# galvanika-board-2_2.net
KiCad netlist of a schematic drawn in EAGLE
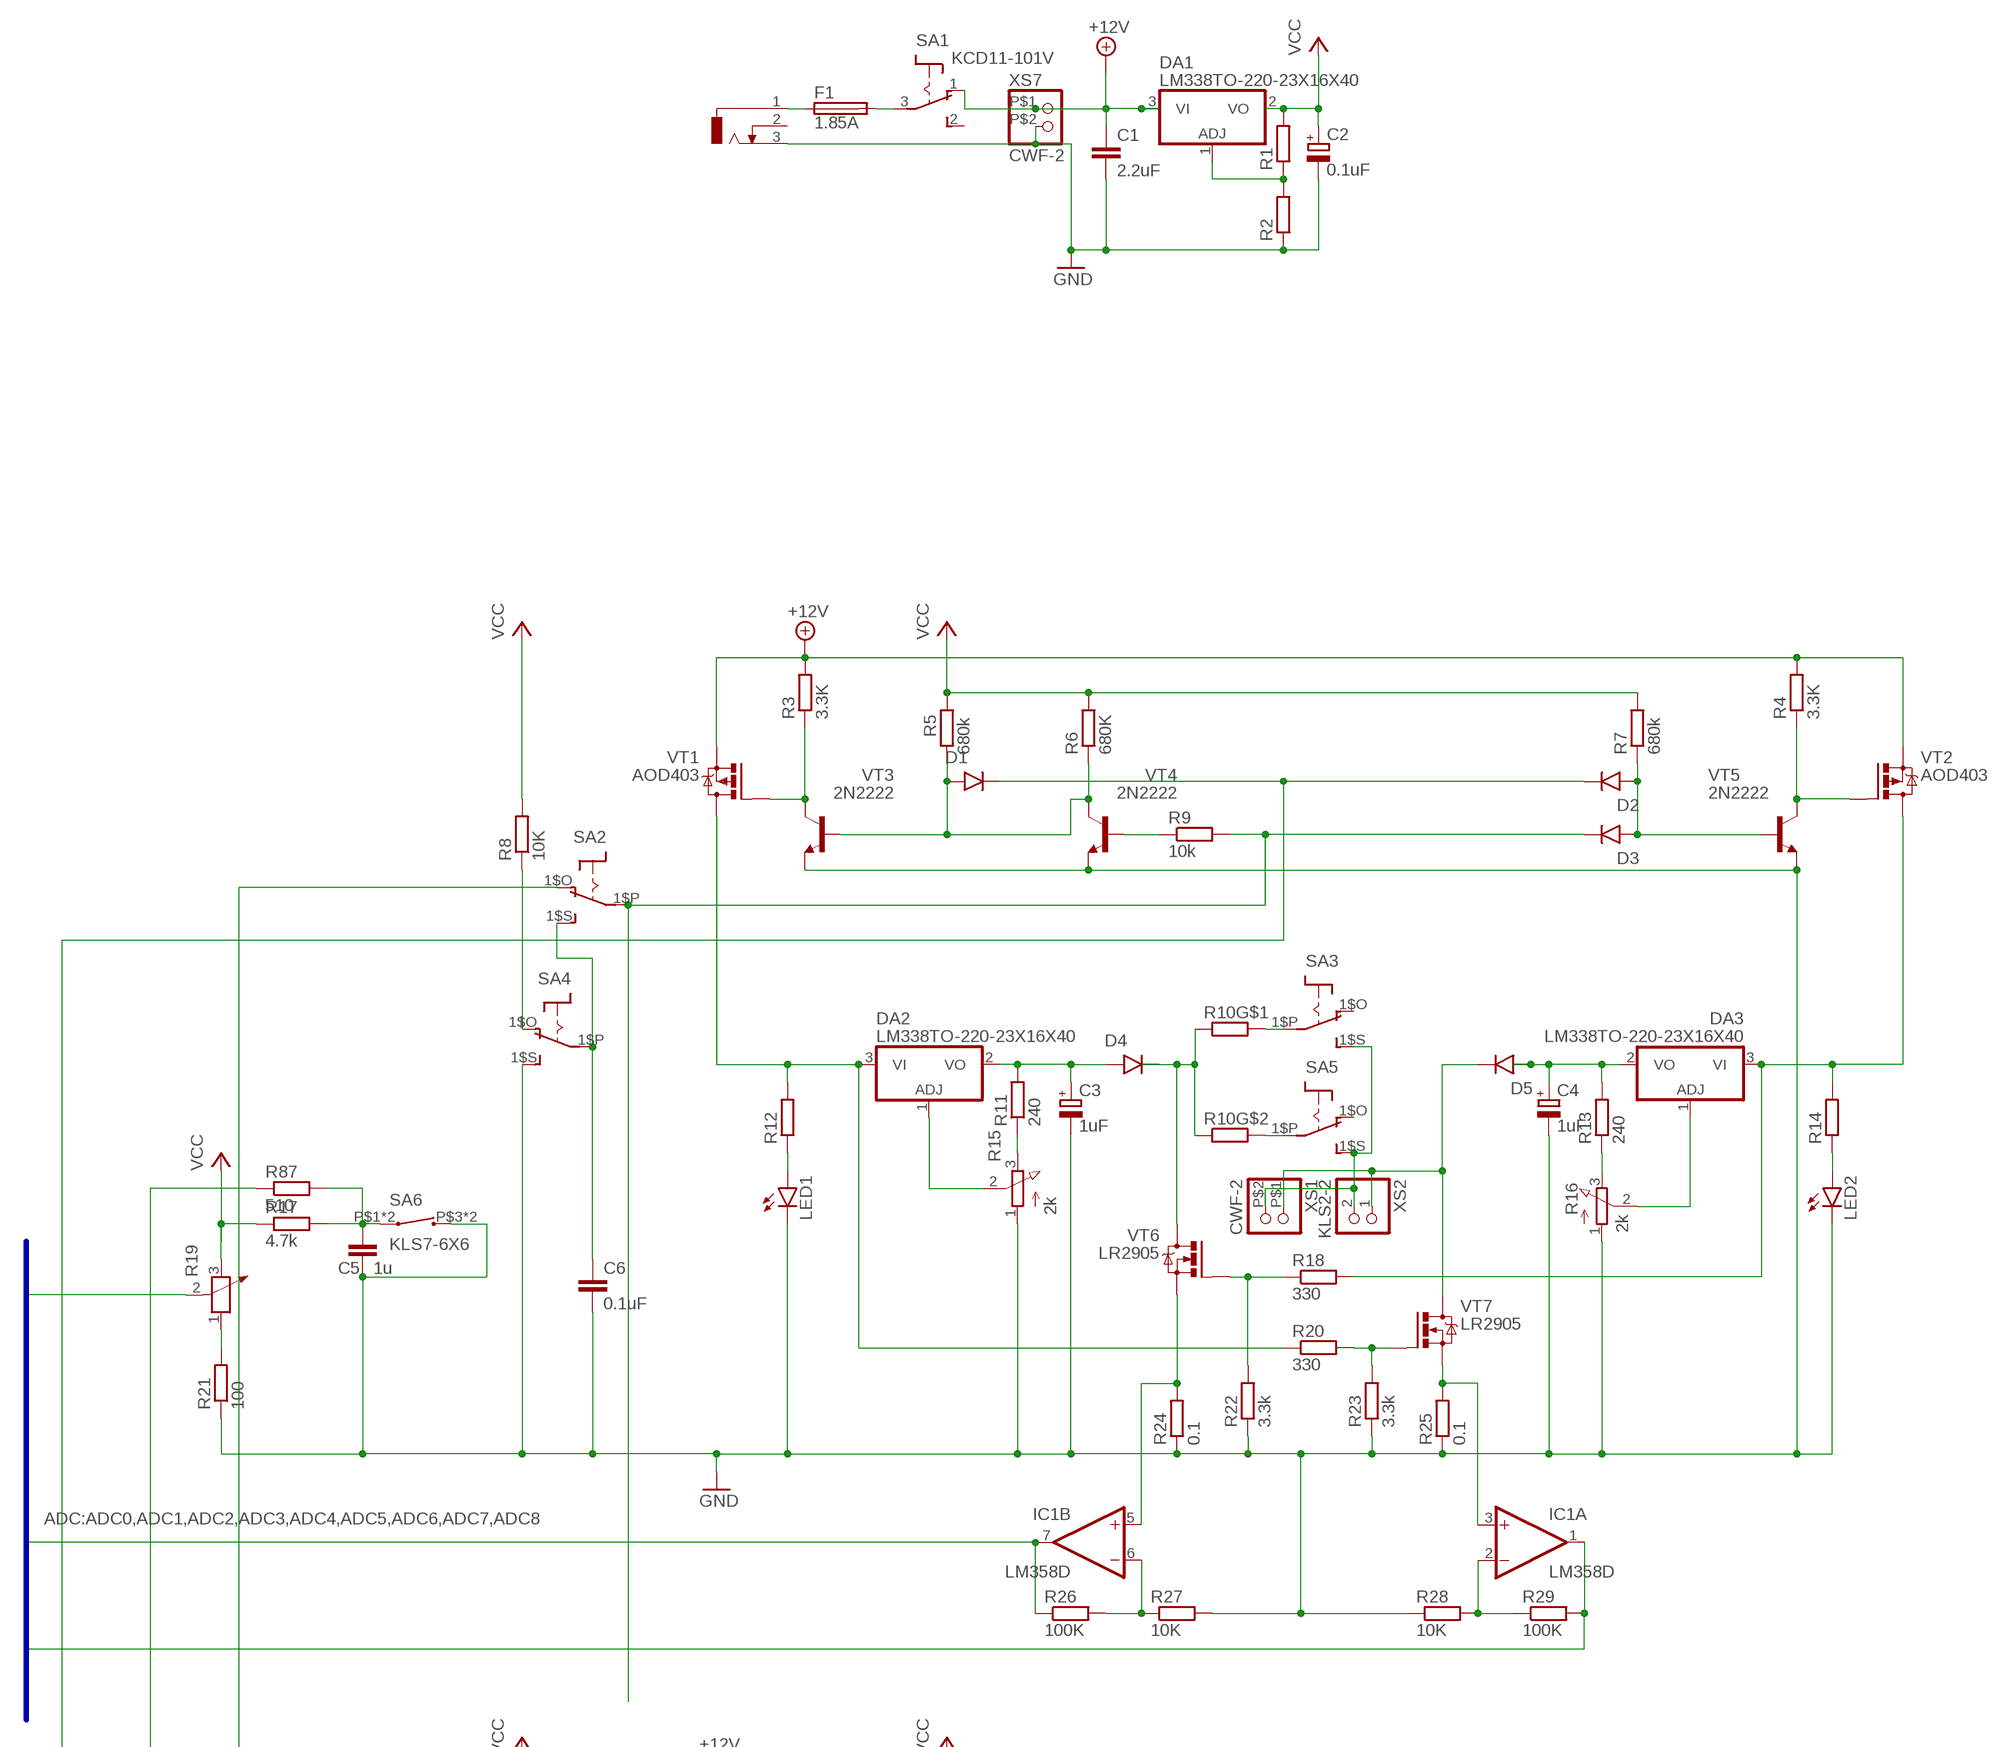
[diagram p0: schematic, sheet 1, part 1 of 2]
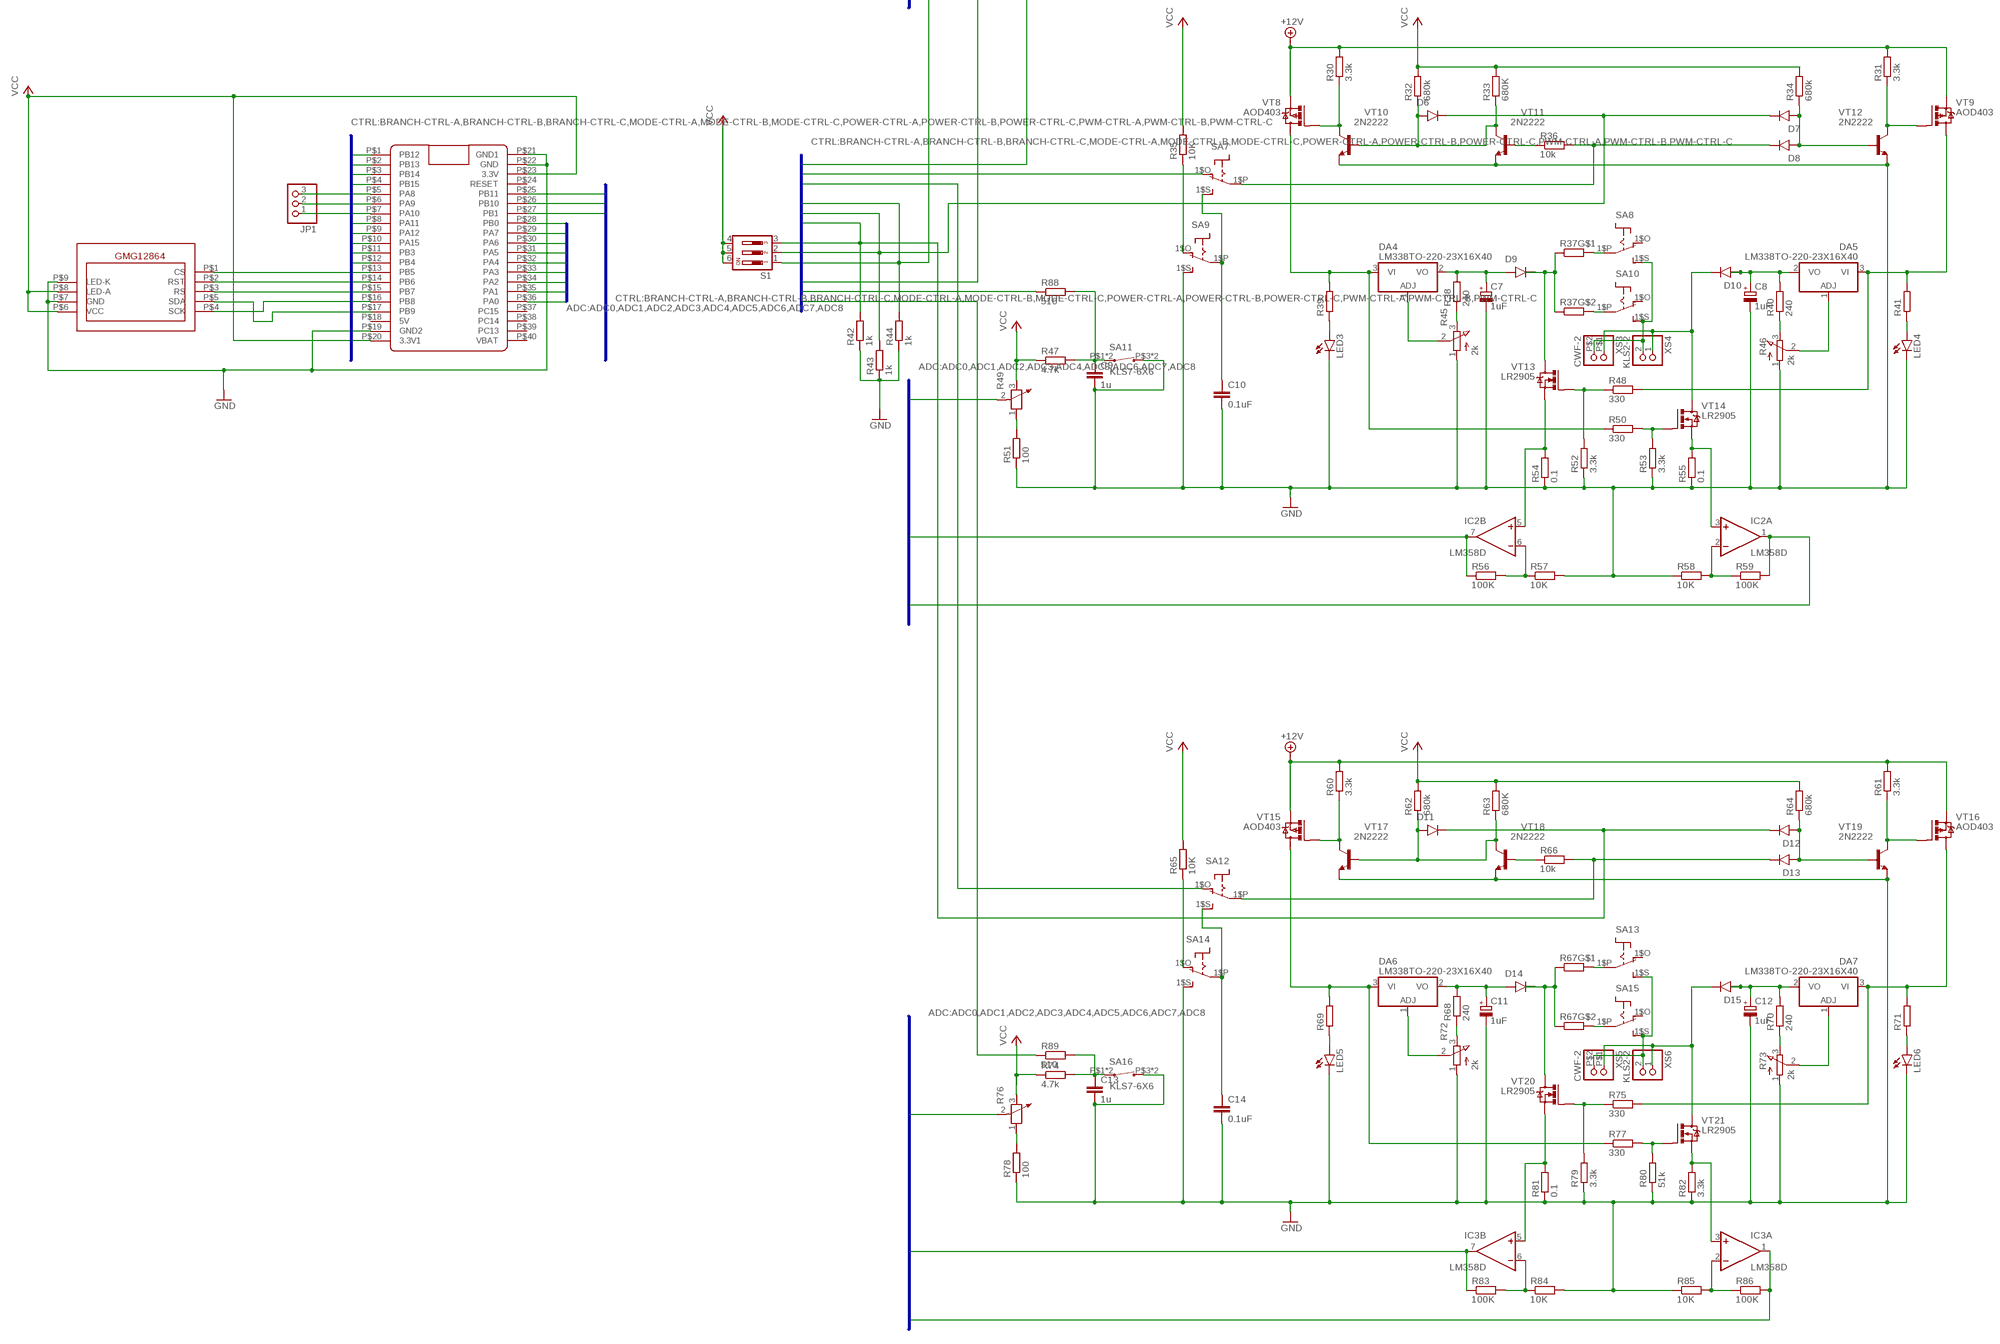
[diagram p1: schematic, sheet 1, part 2 of 2]

(export (version "E")
  (design (tool "Eeschema 10.0.6"))
  (components
    (comp (ref "C1")
      (value "2.2uF")
      (footprint "eagle-import:C025-025X050")
      (libsource (lib "eagle-import") (part "C-EU025-025X050"))
    )
    (comp (ref "C2")
      (value "0.1uF")
      (footprint "eagle-import:E2,5-5")
      (libsource (lib "eagle-import") (part "rcl_334_CPOL-EUE2.5-5"))
    )
    (comp (ref "C3")
      (value "1uF")
      (footprint "eagle-import:E5-4")
      (libsource (lib "eagle-import") (part "CPOL-EUE5-4"))
    )
    (comp (ref "C4")
      (value "1uF")
      (footprint "eagle-import:E5-4")
      (libsource (lib "eagle-import") (part "CPOL-EUE5-4"))
    )
    (comp (ref "C5")
      (value "1u")
      (footprint "eagle-import:C1206")
      (libsource (lib "eagle-import") (part "C-EUC1206"))
    )
    (comp (ref "C6")
      (value "0.1uF")
      (footprint "eagle-import:C1206")
      (libsource (lib "eagle-import") (part "C-EUC1206"))
    )
    (comp (ref "C7")
      (value "1uF")
      (footprint "eagle-import:E5-4")
      (libsource (lib "eagle-import") (part "CPOL-EUE5-4"))
    )
    (comp (ref "C8")
      (value "1uF")
      (footprint "eagle-import:E5-4")
      (libsource (lib "eagle-import") (part "CPOL-EUE5-4"))
    )
    (comp (ref "C9")
      (value "1u")
      (footprint "eagle-import:C1206")
      (libsource (lib "eagle-import") (part "C-EUC1206"))
    )
    (comp (ref "C10")
      (value "0.1uF")
      (footprint "eagle-import:C1206")
      (libsource (lib "eagle-import") (part "C-EUC1206"))
    )
    (comp (ref "C11")
      (value "1uF")
      (footprint "eagle-import:E5-4")
      (libsource (lib "eagle-import") (part "CPOL-EUE5-4"))
    )
    (comp (ref "C12")
      (value "1uF")
      (footprint "eagle-import:E5-4")
      (libsource (lib "eagle-import") (part "CPOL-EUE5-4"))
    )
    (comp (ref "C13")
      (value "1u")
      (footprint "eagle-import:C1206")
      (libsource (lib "eagle-import") (part "C-EUC1206"))
    )
    (comp (ref "C14")
      (value "0.1uF")
      (footprint "eagle-import:C1206")
      (libsource (lib "eagle-import") (part "C-EUC1206"))
    )
    (comp (ref "D1")
      (value "1N4001")
      (footprint "eagle-import:DO41-10")
      (libsource (lib "eagle-import") (part "1N4001"))
    )
    (comp (ref "D2")
      (value "1N4001")
      (footprint "eagle-import:DO41-10")
      (libsource (lib "eagle-import") (part "1N4001"))
    )
    (comp (ref "D3")
      (value "1N4001")
      (footprint "eagle-import:DO41-10")
      (libsource (lib "eagle-import") (part "1N4001"))
    )
    (comp (ref "D4")
      (value "1N4001")
      (footprint "eagle-import:DO41-10")
      (libsource (lib "eagle-import") (part "1N4001"))
    )
    (comp (ref "D5")
      (value "1N4001")
      (footprint "eagle-import:DO41-10")
      (libsource (lib "eagle-import") (part "1N4001"))
    )
    (comp (ref "D6")
      (value "1N4001")
      (footprint "eagle-import:DO41-10")
      (libsource (lib "eagle-import") (part "1N4001"))
    )
    (comp (ref "D7")
      (value "1N4001")
      (footprint "eagle-import:DO41-10")
      (libsource (lib "eagle-import") (part "1N4001"))
    )
    (comp (ref "D8")
      (value "1N4001")
      (footprint "eagle-import:DO41-10")
      (libsource (lib "eagle-import") (part "1N4001"))
    )
    (comp (ref "D9")
      (value "1N4001")
      (footprint "eagle-import:DO41-10")
      (libsource (lib "eagle-import") (part "1N4001"))
    )
    (comp (ref "D10")
      (value "1N4001")
      (footprint "eagle-import:DO41-10")
      (libsource (lib "eagle-import") (part "1N4001"))
    )
    (comp (ref "D11")
      (value "1N4001")
      (footprint "eagle-import:DO41-10")
      (libsource (lib "eagle-import") (part "1N4001"))
    )
    (comp (ref "D12")
      (value "1N4001")
      (footprint "eagle-import:DO41-10")
      (libsource (lib "eagle-import") (part "1N4001"))
    )
    (comp (ref "D13")
      (value "1N4001")
      (footprint "eagle-import:DO41-10")
      (libsource (lib "eagle-import") (part "1N4001"))
    )
    (comp (ref "D14")
      (value "1N4001")
      (footprint "eagle-import:DO41-10")
      (libsource (lib "eagle-import") (part "1N4001"))
    )
    (comp (ref "D15")
      (value "1N4001")
      (footprint "eagle-import:DO41-10")
      (libsource (lib "eagle-import") (part "1N4001"))
    )
    (comp (ref "DA1")
      (value "LM338TO-220-23X16X40")
      (footprint "eagle-import:TO220-23X16X40")
      (libsource (lib "eagle-import") (part "LM338TO-220-23X16X40"))
    )
    (comp (ref "DA2")
      (value "LM338TO-220-23X16X40")
      (footprint "eagle-import:TO220-23X16X40")
      (libsource (lib "eagle-import") (part "LM338TO-220-23X16X40"))
    )
    (comp (ref "DA3")
      (value "LM338TO-220-23X16X40")
      (footprint "eagle-import:TO220-23X16X40")
      (libsource (lib "eagle-import") (part "LM338TO-220-23X16X40"))
    )
    (comp (ref "DA4")
      (value "LM338TO-220-23X16X40")
      (footprint "eagle-import:TO220-23X16X40")
      (libsource (lib "eagle-import") (part "LM338TO-220-23X16X40"))
    )
    (comp (ref "DA5")
      (value "LM338TO-220-23X16X40")
      (footprint "eagle-import:TO220-23X16X40")
      (libsource (lib "eagle-import") (part "LM338TO-220-23X16X40"))
    )
    (comp (ref "DA6")
      (value "LM338TO-220-23X16X40")
      (footprint "eagle-import:TO220-23X16X40")
      (libsource (lib "eagle-import") (part "LM338TO-220-23X16X40"))
    )
    (comp (ref "DA7")
      (value "LM338TO-220-23X16X40")
      (footprint "eagle-import:TO220-23X16X40")
      (libsource (lib "eagle-import") (part "LM338TO-220-23X16X40"))
    )
    (comp (ref "DD1")
      (value "BLUE_PILL")
      (footprint "eagle-import:BLUE_PILL")
      (libsource (lib "eagle-import") (part "BLUE_PILL"))
    )
    (comp (ref "F1")
      (value "1.85A")
      (footprint "eagle-import:MF-R")
      (libsource (lib "eagle-import") (part "MF-R"))
    )
    (comp (ref "HG2")
      (value "GMG1286406D")
      (footprint "eagle-import:GMG12864")
      (libsource (lib "eagle-import") (part "GMG1286406D"))
    )
    (comp (ref "IC1")
      (value "LM358D")
      (footprint "eagle-import:SO08")
      (libsource (lib "eagle-import") (part "LM358D"))
    )
    (comp (ref "IC2")
      (value "LM358D")
      (footprint "eagle-import:SO08")
      (libsource (lib "eagle-import") (part "LM358D"))
    )
    (comp (ref "IC3")
      (value "LM358D")
      (footprint "eagle-import:SO08")
      (libsource (lib "eagle-import") (part "LM358D"))
    )
    (comp (ref "J1")
      (value "DCJ0303")
      (footprint "eagle-import:DCJ0303")
      (libsource (lib "eagle-import") (part "DCJ0303"))
    )
    (comp (ref "JP1")
      (value "PINHD-1X3")
      (footprint "eagle-import:1X03")
      (libsource (lib "eagle-import") (part "PINHD-1X3"))
    )
    (comp (ref "LED1")
      (value "LED3MM")
      (footprint "eagle-import:LED3MM")
      (libsource (lib "eagle-import") (part "LED3MM"))
    )
    (comp (ref "LED2")
      (value "LED3MM")
      (footprint "eagle-import:LED3MM")
      (libsource (lib "eagle-import") (part "LED3MM"))
    )
    (comp (ref "LED3")
      (value "LED3MM")
      (footprint "eagle-import:LED3MM")
      (libsource (lib "eagle-import") (part "LED3MM"))
    )
    (comp (ref "LED4")
      (value "LED3MM")
      (footprint "eagle-import:LED3MM")
      (libsource (lib "eagle-import") (part "LED3MM"))
    )
    (comp (ref "LED5")
      (value "LED3MM")
      (footprint "eagle-import:LED3MM")
      (libsource (lib "eagle-import") (part "LED3MM"))
    )
    (comp (ref "LED6")
      (value "LED3MM")
      (footprint "eagle-import:LED3MM")
      (libsource (lib "eagle-import") (part "LED3MM"))
    )
    (comp (ref "R1")
      (value "R-EU_0207/10")
      (footprint "eagle-import:0207_10")
      (libsource (lib "eagle-import") (part "R-EU_0207/10"))
    )
    (comp (ref "R2")
      (value "R-EU_0207/10")
      (footprint "eagle-import:0207_10")
      (libsource (lib "eagle-import") (part "R-EU_0207/10"))
    )
    (comp (ref "R3")
      (value "3.3K")
      (footprint "eagle-import:0207_10")
      (libsource (lib "eagle-import") (part "rcl_334_R-EU_0207/10"))
    )
    (comp (ref "R4")
      (value "3.3K")
      (footprint "eagle-import:0207_10")
      (libsource (lib "eagle-import") (part "rcl_334_R-EU_0207/10"))
    )
    (comp (ref "R5")
      (value "680k")
      (footprint "eagle-import:0207_10")
      (libsource (lib "eagle-import") (part "rcl_334_R-EU_0207/10"))
    )
    (comp (ref "R6")
      (value "680K")
      (footprint "eagle-import:0207_10")
      (libsource (lib "eagle-import") (part "rcl_334_R-EU_0207/10"))
    )
    (comp (ref "R7")
      (value "680k")
      (footprint "eagle-import:0207_10")
      (libsource (lib "eagle-import") (part "rcl_334_R-EU_0207/10"))
    )
    (comp (ref "R8")
      (value "10K")
      (footprint "eagle-import:0207_10")
      (libsource (lib "eagle-import") (part "rcl_334_R-EU_0207/10"))
    )
    (comp (ref "R9")
      (value "10k")
      (footprint "eagle-import:0207_10")
      (libsource (lib "eagle-import") (part "rcl_334_R-EU_0207/10"))
    )
    (comp (ref "R10")
      (value "SQP-5W-2")
      (footprint "eagle-import:SQP-5W-2")
      (libsource (lib "eagle-import") (part "SQP-5W-2"))
    )
    (comp (ref "R11")
      (value "240")
      (footprint "eagle-import:0207_10")
      (libsource (lib "eagle-import") (part "rcl_334_R-EU_0207/10"))
    )
    (comp (ref "R12")
      (value "R-EU_0207/10")
      (footprint "eagle-import:0207_10")
      (libsource (lib "eagle-import") (part "rcl_334_R-EU_0207/10"))
    )
    (comp (ref "R13")
      (value "240")
      (footprint "eagle-import:0207_10")
      (libsource (lib "eagle-import") (part "rcl_334_R-EU_0207/10"))
    )
    (comp (ref "R14")
      (value "R-EU_0207/10")
      (footprint "eagle-import:0207_10")
      (libsource (lib "eagle-import") (part "rcl_334_R-EU_0207/10"))
    )
    (comp (ref "R15")
      (value "2k")
      (footprint "eagle-import:3RP_1610N")
      (libsource (lib "eagle-import") (part "3RP/1610N"))
    )
    (comp (ref "R16")
      (value "2k")
      (footprint "eagle-import:3RP_1610N")
      (libsource (lib "eagle-import") (part "3RP/1610N"))
    )
    (comp (ref "R17")
      (value "4.7k")
      (footprint "eagle-import:R1206")
      (libsource (lib "eagle-import") (part "R-EU_R1206"))
    )
    (comp (ref "R18")
      (value "330")
      (footprint "eagle-import:0207_10")
      (libsource (lib "eagle-import") (part "rcl_334_R-EU_0207/10"))
    )
    (comp (ref "R19")
      (value "R0904N")
      (footprint "eagle-import:R0904N")
      (libsource (lib "eagle-import") (part "R0904N"))
    )
    (comp (ref "R20")
      (value "330")
      (footprint "eagle-import:0207_10")
      (libsource (lib "eagle-import") (part "rcl_334_R-EU_0207/10"))
    )
    (comp (ref "R21")
      (value "100")
      (footprint "eagle-import:R1206")
      (libsource (lib "eagle-import") (part "R-EU_R1206"))
    )
    (comp (ref "R22")
      (value "3.3k")
      (footprint "eagle-import:0207_10")
      (libsource (lib "eagle-import") (part "rcl_334_R-EU_0207/10"))
    )
    (comp (ref "R23")
      (value "3.3k")
      (footprint "eagle-import:0207_10")
      (libsource (lib "eagle-import") (part "rcl_334_R-EU_0207/10"))
    )
    (comp (ref "R24")
      (value "0.1")
      (footprint "eagle-import:0411_12")
      (libsource (lib "eagle-import") (part "rcl_334_R-EU_0411/12"))
    )
    (comp (ref "R25")
      (value "0.1")
      (footprint "eagle-import:0411_12")
      (libsource (lib "eagle-import") (part "rcl_334_R-EU_0411/12"))
    )
    (comp (ref "R26")
      (value "100K")
      (footprint "eagle-import:R1206")
      (libsource (lib "eagle-import") (part "rcl_334_R-EU_R1206"))
    )
    (comp (ref "R27")
      (value "10K")
      (footprint "eagle-import:R1206")
      (libsource (lib "eagle-import") (part "rcl_334_R-EU_R1206"))
    )
    (comp (ref "R28")
      (value "10K")
      (footprint "eagle-import:R1206")
      (libsource (lib "eagle-import") (part "rcl_334_R-EU_R1206"))
    )
    (comp (ref "R29")
      (value "100K")
      (footprint "eagle-import:R1206")
      (libsource (lib "eagle-import") (part "rcl_334_R-EU_R1206"))
    )
    (comp (ref "R30")
      (value "3.3k")
      (footprint "eagle-import:0207_10")
      (libsource (lib "eagle-import") (part "rcl_334_R-EU_0207/10"))
    )
    (comp (ref "R31")
      (value "3.3k")
      (footprint "eagle-import:0207_10")
      (libsource (lib "eagle-import") (part "rcl_334_R-EU_0207/10"))
    )
    (comp (ref "R32")
      (value "680k")
      (footprint "eagle-import:0207_10")
      (libsource (lib "eagle-import") (part "rcl_334_R-EU_0207/10"))
    )
    (comp (ref "R33")
      (value "680K")
      (footprint "eagle-import:0207_10")
      (libsource (lib "eagle-import") (part "rcl_334_R-EU_0207/10"))
    )
    (comp (ref "R34")
      (value "680k")
      (footprint "eagle-import:0207_10")
      (libsource (lib "eagle-import") (part "rcl_334_R-EU_0207/10"))
    )
    (comp (ref "R35")
      (value "10K")
      (footprint "eagle-import:0207_10")
      (libsource (lib "eagle-import") (part "rcl_334_R-EU_0207/10"))
    )
    (comp (ref "R36")
      (value "10k")
      (footprint "eagle-import:0207_10")
      (libsource (lib "eagle-import") (part "rcl_334_R-EU_0207/10"))
    )
    (comp (ref "R37")
      (value "SQP-5W-2")
      (footprint "eagle-import:SQP-5W-2")
      (libsource (lib "eagle-import") (part "SQP-5W-2"))
    )
    (comp (ref "R38")
      (value "240")
      (footprint "eagle-import:0207_10")
      (libsource (lib "eagle-import") (part "R-EU_0207/10"))
    )
    (comp (ref "R39")
      (value "R-EU_0207/10")
      (footprint "eagle-import:0207_10")
      (libsource (lib "eagle-import") (part "R-EU_0207/10"))
    )
    (comp (ref "R40")
      (value "240")
      (footprint "eagle-import:0207_10")
      (libsource (lib "eagle-import") (part "rcl_334_R-EU_0207/10"))
    )
    (comp (ref "R41")
      (value "R-EU_0207/10")
      (footprint "eagle-import:0207_10")
      (libsource (lib "eagle-import") (part "R-EU_0207/10"))
    )
    (comp (ref "R42")
      (value "1k")
      (footprint "eagle-import:R1206")
      (libsource (lib "eagle-import") (part "R-EU_R1206"))
    )
    (comp (ref "R43")
      (value "1k")
      (footprint "eagle-import:R1206")
      (libsource (lib "eagle-import") (part "R-EU_R1206"))
    )
    (comp (ref "R44")
      (value "1k")
      (footprint "eagle-import:R1206")
      (libsource (lib "eagle-import") (part "R-EU_R1206"))
    )
    (comp (ref "R45")
      (value "2k")
      (footprint "eagle-import:3RP_1610N")
      (libsource (lib "eagle-import") (part "3RP/1610N"))
    )
    (comp (ref "R46")
      (value "2k")
      (footprint "eagle-import:3RP_1610N")
      (libsource (lib "eagle-import") (part "3RP/1610N"))
    )
    (comp (ref "R47")
      (value "4.7k")
      (footprint "eagle-import:R1206")
      (libsource (lib "eagle-import") (part "R-EU_R1206"))
    )
    (comp (ref "R48")
      (value "330")
      (footprint "eagle-import:0207_10")
      (libsource (lib "eagle-import") (part "rcl_334_R-EU_0207/10"))
    )
    (comp (ref "R49")
      (value "R0904N")
      (footprint "eagle-import:R0904N")
      (libsource (lib "eagle-import") (part "R0904N"))
    )
    (comp (ref "R50")
      (value "330")
      (footprint "eagle-import:0207_10")
      (libsource (lib "eagle-import") (part "rcl_334_R-EU_0207/10"))
    )
    (comp (ref "R51")
      (value "100")
      (footprint "eagle-import:R1206")
      (libsource (lib "eagle-import") (part "R-EU_R1206"))
    )
    (comp (ref "R52")
      (value "3.3k")
      (footprint "eagle-import:0207_10")
      (libsource (lib "eagle-import") (part "rcl_334_R-EU_0207/10"))
    )
    (comp (ref "R53")
      (value "3.3k")
      (footprint "eagle-import:0207_10")
      (libsource (lib "eagle-import") (part "rcl_334_R-EU_0207/10"))
    )
    (comp (ref "R54")
      (value "0.1")
      (footprint "eagle-import:0411_12")
      (libsource (lib "eagle-import") (part "rcl_334_R-EU_0411/12"))
    )
    (comp (ref "R55")
      (value "0.1")
      (footprint "eagle-import:0411_12")
      (libsource (lib "eagle-import") (part "rcl_334_R-EU_0411/12"))
    )
    (comp (ref "R56")
      (value "100K")
      (footprint "eagle-import:R1206")
      (libsource (lib "eagle-import") (part "rcl_334_R-EU_R1206"))
    )
    (comp (ref "R57")
      (value "10K")
      (footprint "eagle-import:R1206")
      (libsource (lib "eagle-import") (part "rcl_334_R-EU_R1206"))
    )
    (comp (ref "R58")
      (value "10K")
      (footprint "eagle-import:R1206")
      (libsource (lib "eagle-import") (part "rcl_334_R-EU_R1206"))
    )
    (comp (ref "R59")
      (value "100K")
      (footprint "eagle-import:R1206")
      (libsource (lib "eagle-import") (part "rcl_334_R-EU_R1206"))
    )
    (comp (ref "R60")
      (value "3.3k")
      (footprint "eagle-import:0207_10")
      (libsource (lib "eagle-import") (part "rcl_334_R-EU_0207/10"))
    )
    (comp (ref "R61")
      (value "3.3k")
      (footprint "eagle-import:0207_10")
      (libsource (lib "eagle-import") (part "rcl_334_R-EU_0207/10"))
    )
    (comp (ref "R62")
      (value "680k")
      (footprint "eagle-import:0207_10")
      (libsource (lib "eagle-import") (part "rcl_334_R-EU_0207/10"))
    )
    (comp (ref "R63")
      (value "680K")
      (footprint "eagle-import:0207_10")
      (libsource (lib "eagle-import") (part "rcl_334_R-EU_0207/10"))
    )
    (comp (ref "R64")
      (value "680k")
      (footprint "eagle-import:0207_10")
      (libsource (lib "eagle-import") (part "rcl_334_R-EU_0207/10"))
    )
    (comp (ref "R65")
      (value "10K")
      (footprint "eagle-import:0207_10")
      (libsource (lib "eagle-import") (part "rcl_334_R-EU_0207/10"))
    )
    (comp (ref "R66")
      (value "10k")
      (footprint "eagle-import:0207_10")
      (libsource (lib "eagle-import") (part "rcl_334_R-EU_0207/10"))
    )
    (comp (ref "R67")
      (value "SQP-5W-2")
      (footprint "eagle-import:SQP-5W-2")
      (libsource (lib "eagle-import") (part "SQP-5W-2"))
    )
    (comp (ref "R68")
      (value "240")
      (footprint "eagle-import:0207_10")
      (libsource (lib "eagle-import") (part "rcl_334_R-EU_0207/10"))
    )
    (comp (ref "R69")
      (value "R-EU_0207/10")
      (footprint "eagle-import:0207_10")
      (libsource (lib "eagle-import") (part "rcl_334_R-EU_0207/10"))
    )
    (comp (ref "R70")
      (value "240")
      (footprint "eagle-import:0207_10")
      (libsource (lib "eagle-import") (part "rcl_334_R-EU_0207/10"))
    )
    (comp (ref "R71")
      (value "R-EU_0207/10")
      (footprint "eagle-import:0207_10")
      (libsource (lib "eagle-import") (part "rcl_334_R-EU_0207/10"))
    )
    (comp (ref "R72")
      (value "2k")
      (footprint "eagle-import:3RP_1610N")
      (libsource (lib "eagle-import") (part "3RP/1610N"))
    )
    (comp (ref "R73")
      (value "2k")
      (footprint "eagle-import:3RP_1610N")
      (libsource (lib "eagle-import") (part "3RP/1610N"))
    )
    (comp (ref "R74")
      (value "4.7k")
      (footprint "eagle-import:R1206")
      (libsource (lib "eagle-import") (part "R-EU_R1206"))
    )
    (comp (ref "R75")
      (value "330")
      (footprint "eagle-import:0207_10")
      (libsource (lib "eagle-import") (part "rcl_334_R-EU_0207/10"))
    )
    (comp (ref "R76")
      (value "R0904N")
      (footprint "eagle-import:R0904N")
      (libsource (lib "eagle-import") (part "R0904N"))
    )
    (comp (ref "R77")
      (value "330")
      (footprint "eagle-import:0207_10")
      (libsource (lib "eagle-import") (part "rcl_334_R-EU_0207/10"))
    )
    (comp (ref "R78")
      (value "100")
      (footprint "eagle-import:R1206")
      (libsource (lib "eagle-import") (part "R-EU_R1206"))
    )
    (comp (ref "R79")
      (value "3.3k")
      (footprint "eagle-import:0207_10")
      (libsource (lib "eagle-import") (part "rcl_334_R-EU_0207/10"))
    )
    (comp (ref "R80")
      (value "51k")
      (footprint "eagle-import:0207_10")
      (libsource (lib "eagle-import") (part "rcl_334_R-EU_0207/10"))
    )
    (comp (ref "R81")
      (value "0.1")
      (footprint "eagle-import:0411_12")
      (libsource (lib "eagle-import") (part "rcl_334_R-EU_0411/12"))
    )
    (comp (ref "R82")
      (value "3.3k")
      (footprint "eagle-import:0411_12")
      (libsource (lib "eagle-import") (part "rcl_334_R-EU_0411/12"))
    )
    (comp (ref "R83")
      (value "100K")
      (footprint "eagle-import:R1206")
      (libsource (lib "eagle-import") (part "rcl_334_R-EU_R1206"))
    )
    (comp (ref "R84")
      (value "10K")
      (footprint "eagle-import:R1206")
      (libsource (lib "eagle-import") (part "rcl_334_R-EU_R1206"))
    )
    (comp (ref "R85")
      (value "10K")
      (footprint "eagle-import:R1206")
      (libsource (lib "eagle-import") (part "rcl_334_R-EU_R1206"))
    )
    (comp (ref "R86")
      (value "100K")
      (footprint "eagle-import:R1206")
      (libsource (lib "eagle-import") (part "rcl_334_R-EU_R1206"))
    )
    (comp (ref "R87")
      (value "510")
      (footprint "eagle-import:R1206")
      (libsource (lib "eagle-import") (part "R-EU_R1206"))
    )
    (comp (ref "R88")
      (value "510")
      (footprint "eagle-import:R1206")
      (libsource (lib "eagle-import") (part "R-EU_R1206"))
    )
    (comp (ref "R89")
      (value "510")
      (footprint "eagle-import:R1206")
      (libsource (lib "eagle-import") (part "R-EU_R1206"))
    )
    (comp (ref "S1")
      (value "DS03")
      (footprint "eagle-import:DS-03")
      (libsource (lib "eagle-import") (part "DS03"))
    )
    (comp (ref "SA1")
      (value "KCD11-101V")
      (footprint "eagle-import:KCD11-101-V")
      (libsource (lib "eagle-import") (part "KCD11-101V"))
    )
    (comp (ref "SA2")
      (value "SS12D00DIP")
      (footprint "eagle-import:SS12D00")
      (libsource (lib "eagle-import") (part "SS12D00DIP"))
    )
    (comp (ref "SA3")
      (value "SS12D00DIP")
      (footprint "eagle-import:SS12D00")
      (libsource (lib "eagle-import") (part "SS12D00DIP"))
    )
    (comp (ref "SA4")
      (value "SS12D00DIP")
      (footprint "eagle-import:SS12D00")
      (libsource (lib "eagle-import") (part "SS12D00DIP"))
    )
    (comp (ref "SA5")
      (value "SS12D00DIP")
      (footprint "eagle-import:SS12D00")
      (libsource (lib "eagle-import") (part "SS12D00DIP"))
    )
    (comp (ref "SA6")
      (value "KLS7-6X6")
      (footprint "eagle-import:KLS7-6X6")
      (libsource (lib "eagle-import") (part "KLS7-6X6"))
    )
    (comp (ref "SA7")
      (value "SS12D00DIP")
      (footprint "eagle-import:SS12D00")
      (libsource (lib "eagle-import") (part "SS12D00DIP"))
    )
    (comp (ref "SA8")
      (value "SS12D00DIP")
      (footprint "eagle-import:SS12D00")
      (libsource (lib "eagle-import") (part "SS12D00DIP"))
    )
    (comp (ref "SA9")
      (value "SS12D00DIP")
      (footprint "eagle-import:SS12D00")
      (libsource (lib "eagle-import") (part "SS12D00DIP"))
    )
    (comp (ref "SA10")
      (value "SS12D00DIP")
      (footprint "eagle-import:SS12D00")
      (libsource (lib "eagle-import") (part "SS12D00DIP"))
    )
    (comp (ref "SA11")
      (value "KLS7-6X6")
      (footprint "eagle-import:KLS7-6X6")
      (libsource (lib "eagle-import") (part "KLS7-6X6"))
    )
    (comp (ref "SA12")
      (value "SS12D00DIP")
      (footprint "eagle-import:SS12D00")
      (libsource (lib "eagle-import") (part "SS12D00DIP"))
    )
    (comp (ref "SA13")
      (value "SS12D00DIP")
      (footprint "eagle-import:SS12D00")
      (libsource (lib "eagle-import") (part "SS12D00DIP"))
    )
    (comp (ref "SA14")
      (value "SS12D00DIP")
      (footprint "eagle-import:SS12D00")
      (libsource (lib "eagle-import") (part "SS12D00DIP"))
    )
    (comp (ref "SA15")
      (value "SS12D00DIP")
      (footprint "eagle-import:SS12D00")
      (libsource (lib "eagle-import") (part "SS12D00DIP"))
    )
    (comp (ref "SA16")
      (value "KLS7-6X6")
      (footprint "eagle-import:KLS7-6X6")
      (libsource (lib "eagle-import") (part "KLS7-6X6"))
    )
    (comp (ref "VT1")
      (value "AOD403")
      (footprint "eagle-import:TO252")
      (libsource (lib "eagle-import") (part "AOD403"))
    )
    (comp (ref "VT2")
      (value "AOD403")
      (footprint "eagle-import:TO252")
      (libsource (lib "eagle-import") (part "AOD403"))
    )
    (comp (ref "VT3")
      (value "2N2222")
      (footprint "eagle-import:TO92")
      (libsource (lib "eagle-import") (part "2N2222"))
    )
    (comp (ref "VT4")
      (value "2N2222")
      (footprint "eagle-import:TO92")
      (libsource (lib "eagle-import") (part "2N2222"))
    )
    (comp (ref "VT5")
      (value "2N2222")
      (footprint "eagle-import:TO92")
      (libsource (lib "eagle-import") (part "2N2222"))
    )
    (comp (ref "VT6")
      (value "LR2905")
      (footprint "eagle-import:TO252")
      (libsource (lib "eagle-import") (part "LR2905"))
    )
    (comp (ref "VT7")
      (value "LR2905")
      (footprint "eagle-import:TO252")
      (libsource (lib "eagle-import") (part "LR2905"))
    )
    (comp (ref "VT8")
      (value "AOD403")
      (footprint "eagle-import:TO252")
      (libsource (lib "eagle-import") (part "AOD403"))
    )
    (comp (ref "VT9")
      (value "AOD403")
      (footprint "eagle-import:TO252")
      (libsource (lib "eagle-import") (part "AOD403"))
    )
    (comp (ref "VT10")
      (value "2N2222")
      (footprint "eagle-import:TO92")
      (libsource (lib "eagle-import") (part "2N2222"))
    )
    (comp (ref "VT11")
      (value "2N2222")
      (footprint "eagle-import:TO92")
      (libsource (lib "eagle-import") (part "2N2222"))
    )
    (comp (ref "VT12")
      (value "2N2222")
      (footprint "eagle-import:TO92")
      (libsource (lib "eagle-import") (part "2N2222"))
    )
    (comp (ref "VT13")
      (value "LR2905")
      (footprint "eagle-import:TO252")
      (libsource (lib "eagle-import") (part "LR2905"))
    )
    (comp (ref "VT14")
      (value "LR2905")
      (footprint "eagle-import:TO252")
      (libsource (lib "eagle-import") (part "LR2905"))
    )
    (comp (ref "VT15")
      (value "AOD403")
      (footprint "eagle-import:TO252")
      (libsource (lib "eagle-import") (part "AOD403"))
    )
    (comp (ref "VT16")
      (value "AOD403")
      (footprint "eagle-import:TO252")
      (libsource (lib "eagle-import") (part "AOD403"))
    )
    (comp (ref "VT17")
      (value "2N2222")
      (footprint "eagle-import:TO92")
      (libsource (lib "eagle-import") (part "2N2222"))
    )
    (comp (ref "VT18")
      (value "2N2222")
      (footprint "eagle-import:TO92")
      (libsource (lib "eagle-import") (part "2N2222"))
    )
    (comp (ref "VT19")
      (value "2N2222")
      (footprint "eagle-import:TO92")
      (libsource (lib "eagle-import") (part "2N2222"))
    )
    (comp (ref "VT20")
      (value "LR2905")
      (footprint "eagle-import:TO252")
      (libsource (lib "eagle-import") (part "LR2905"))
    )
    (comp (ref "VT21")
      (value "LR2905")
      (footprint "eagle-import:TO252")
      (libsource (lib "eagle-import") (part "LR2905"))
    )
    (comp (ref "XS1")
      (value "CWF-2")
      (footprint "eagle-import:CWF-2")
      (libsource (lib "eagle-import") (part "CWF-2"))
    )
    (comp (ref "XS2")
      (value "KLS2-2")
      (footprint "eagle-import:KLS2-2")
      (libsource (lib "eagle-import") (part "KLS2-2"))
    )
    (comp (ref "XS3")
      (value "CWF-2")
      (footprint "eagle-import:CWF-2")
      (libsource (lib "eagle-import") (part "CWF-2"))
    )
    (comp (ref "XS4")
      (value "KLS2-2")
      (footprint "eagle-import:KLS2-2")
      (libsource (lib "eagle-import") (part "KLS2-2"))
    )
    (comp (ref "XS5")
      (value "CWF-2")
      (footprint "eagle-import:CWF-2")
      (libsource (lib "eagle-import") (part "CWF-2"))
    )
    (comp (ref "XS6")
      (value "KLS2-2")
      (footprint "eagle-import:KLS2-2")
      (libsource (lib "eagle-import") (part "KLS2-2"))
    )
    (comp (ref "XS7")
      (value "CWF-2")
      (footprint "eagle-import:CWF-2")
      (libsource (lib "eagle-import") (part "CWF-2"))
    )
  )
  (nets
    (net (code "3") (name "+12V") (class "Default")
      (node (ref "C1") (pin "1") (pinfunction "1_1") (pintype "passive"))
      (node (ref "DA1") (pin "3") (pinfunction "VI_3") (pintype "input"))
      (node (ref "R3") (pin "2") (pinfunction "2_2") (pintype "passive"))
      (node (ref "R30") (pin "2") (pinfunction "2_2") (pintype "passive"))
      (node (ref "R31") (pin "2") (pinfunction "2_2") (pintype "passive"))
      (node (ref "R4") (pin "2") (pinfunction "2_2") (pintype "passive"))
      (node (ref "R60") (pin "2") (pinfunction "2_2") (pintype "passive"))
      (node (ref "R61") (pin "2") (pinfunction "2_2") (pintype "passive"))
      (node (ref "SA1") (pin "1") (pinfunction "O_1") (pintype "passive"))
      (node (ref "VT1") (pin "2") (pinfunction "S_2") (pintype "passive"))
      (node (ref "VT15") (pin "2") (pinfunction "S_2") (pintype "passive"))
      (node (ref "VT16") (pin "2") (pinfunction "S_2") (pintype "passive"))
      (node (ref "VT2") (pin "2") (pinfunction "S_2") (pintype "passive"))
      (node (ref "VT8") (pin "2") (pinfunction "S_2") (pintype "passive"))
      (node (ref "VT9") (pin "2") (pinfunction "S_2") (pintype "passive"))
      (node (ref "XS7") (pin "P$1") (pinfunction "1_P$1") (pintype "passive"))
    )
    (net (code "4") (name "/ADC0") (class "Default")
      (node (ref "DD1") (pin "P$36") (pinfunction "PA0_P$36") (pintype "bidirectional"))
      (node (ref "R19") (pin "2") (pinfunction "3_2") (pintype "passive"))
    )
    (net (code "5") (name "/ADC1") (class "Default")
      (node (ref "DD1") (pin "P$35") (pinfunction "PA1_P$35") (pintype "bidirectional"))
      (node (ref "R49") (pin "2") (pinfunction "3_2") (pintype "passive"))
    )
    (net (code "6") (name "/ADC2") (class "Default")
      (node (ref "DD1") (pin "P$34") (pinfunction "PA2_P$34") (pintype "bidirectional"))
      (node (ref "IC1") (pin "7") (pinfunction "OUT_7") (pintype "output"))
      (node (ref "R26") (pin "1") (pinfunction "1_1") (pintype "passive"))
    )
    (net (code "7") (name "/ADC3") (class "Default")
      (node (ref "DD1") (pin "P$33") (pinfunction "PA3_P$33") (pintype "bidirectional"))
      (node (ref "IC1") (pin "1") (pinfunction "OUT_1") (pintype "output"))
      (node (ref "R29") (pin "2") (pinfunction "2_2") (pintype "passive"))
    )
    (net (code "8") (name "/ADC4") (class "Default")
      (node (ref "DD1") (pin "P$32") (pinfunction "PA4_P$32") (pintype "bidirectional"))
      (node (ref "R76") (pin "2") (pinfunction "3_2") (pintype "passive"))
    )
    (net (code "9") (name "/ADC5") (class "Default")
      (node (ref "DD1") (pin "P$31") (pinfunction "PA5_P$31") (pintype "bidirectional"))
      (node (ref "IC2") (pin "1") (pinfunction "OUT_1") (pintype "output"))
      (node (ref "R59") (pin "2") (pinfunction "2_2") (pintype "passive"))
    )
    (net (code "10") (name "/ADC6") (class "Default")
      (node (ref "DD1") (pin "P$30") (pinfunction "PA6_P$30") (pintype "bidirectional"))
      (node (ref "IC2") (pin "7") (pinfunction "OUT_7") (pintype "output"))
      (node (ref "R56") (pin "1") (pinfunction "1_1") (pintype "passive"))
    )
    (net (code "11") (name "/ADC7") (class "Default")
      (node (ref "DD1") (pin "P$29") (pinfunction "PA7_P$29") (pintype "bidirectional"))
      (node (ref "IC3") (pin "7") (pinfunction "OUT_7") (pintype "output"))
      (node (ref "R83") (pin "1") (pinfunction "1_1") (pintype "passive"))
    )
    (net (code "12") (name "/ADC8") (class "Default")
      (node (ref "DD1") (pin "P$28") (pinfunction "PB0_P$28") (pintype "bidirectional"))
      (node (ref "IC3") (pin "1") (pinfunction "OUT_1") (pintype "output"))
      (node (ref "R86") (pin "2") (pinfunction "2_2") (pintype "passive"))
    )
    (net (code "13") (name "/BRANCH-CTRL-A") (class "Default")
      (node (ref "D3") (pin "C") (pinfunction "CATHODE_C") (pintype "passive"))
      (node (ref "DD1") (pin "P$9") (pinfunction "PA12_P$9") (pintype "bidirectional"))
      (node (ref "R9") (pin "2") (pinfunction "2_2") (pintype "passive"))
      (node (ref "SA2") (pin "1$P") (pinfunction "P_1$P") (pintype "passive"))
    )
    (net (code "14") (name "/BRANCH-CTRL-B") (class "Default")
      (node (ref "D8") (pin "C") (pinfunction "CATHODE_C") (pintype "passive"))
      (node (ref "DD1") (pin "P$8") (pinfunction "PA11_P$8") (pintype "bidirectional"))
      (node (ref "R36") (pin "2") (pinfunction "2_2") (pintype "passive"))
      (node (ref "SA7") (pin "1$P") (pinfunction "P_1$P") (pintype "passive"))
    )
    (net (code "15") (name "/BRANCH-CTRL-C") (class "Default")
      (node (ref "D13") (pin "C") (pinfunction "CATHODE_C") (pintype "passive"))
      (node (ref "DD1") (pin "P$4") (pinfunction "PB15_P$4") (pintype "bidirectional"))
      (node (ref "R66") (pin "2") (pinfunction "2_2") (pintype "passive"))
      (node (ref "SA12") (pin "1$P") (pinfunction "P_1$P") (pintype "passive"))
    )
    (net (code "16") (name "/MODE-CTRL-A") (class "Default")
      (node (ref "DD1") (pin "P$12") (pinfunction "PB4_P$12") (pintype "bidirectional"))
      (node (ref "R87") (pin "1") (pinfunction "1_1") (pintype "passive"))
    )
    (net (code "17") (name "/MODE-CTRL-B") (class "Default")
      (node (ref "DD1") (pin "P$11") (pinfunction "PB3_P$11") (pintype "bidirectional"))
      (node (ref "R88") (pin "1") (pinfunction "1_1") (pintype "passive"))
    )
    (net (code "18") (name "/MODE-CTRL-C") (class "Default")
      (node (ref "DD1") (pin "P$10") (pinfunction "PA15_P$10") (pintype "bidirectional"))
      (node (ref "R89") (pin "1") (pinfunction "1_1") (pintype "passive"))
    )
    (net (code "19") (name "/POWER-CTRL-A") (class "Default")
      (node (ref "D1") (pin "C") (pinfunction "CATHODE_C") (pintype "passive"))
      (node (ref "D2") (pin "C") (pinfunction "CATHODE_C") (pintype "passive"))
      (node (ref "DD1") (pin "P$27") (pinfunction "PB1_P$27") (pintype "bidirectional"))
      (node (ref "R44") (pin "2") (pinfunction "2_2") (pintype "passive"))
      (node (ref "S1") (pin "1") (pinfunction "1_1") (pintype "passive"))
    )
    (net (code "20") (name "/POWER-CTRL-B") (class "Default")
      (node (ref "D6") (pin "C") (pinfunction "CATHODE_C") (pintype "passive"))
      (node (ref "D7") (pin "C") (pinfunction "CATHODE_C") (pintype "passive"))
      (node (ref "DD1") (pin "P$26") (pinfunction "PB10_P$26") (pintype "bidirectional"))
      (node (ref "R43") (pin "2") (pinfunction "2_2") (pintype "passive"))
      (node (ref "S1") (pin "2") (pinfunction "2_2") (pintype "passive"))
    )
    (net (code "21") (name "/POWER-CTRL-C") (class "Default")
      (node (ref "D11") (pin "C") (pinfunction "CATHODE_C") (pintype "passive"))
      (node (ref "D12") (pin "C") (pinfunction "CATHODE_C") (pintype "passive"))
      (node (ref "DD1") (pin "P$25") (pinfunction "PB11_P$25") (pintype "bidirectional"))
      (node (ref "R42") (pin "2") (pinfunction "2_2") (pintype "passive"))
      (node (ref "S1") (pin "3") (pinfunction "3_3") (pintype "passive"))
    )
    (net (code "22") (name "/PWM-CTRL-A") (class "Default")
      (node (ref "DD1") (pin "P$2") (pinfunction "PB13_P$2") (pintype "bidirectional"))
      (node (ref "SA2") (pin "1$O") (pinfunction "O_1$O") (pintype "passive"))
    )
    (net (code "23") (name "/PWM-CTRL-B") (class "Default")
      (node (ref "DD1") (pin "P$3") (pinfunction "PB14_P$3") (pintype "bidirectional"))
      (node (ref "SA7") (pin "1$O") (pinfunction "O_1$O") (pintype "passive"))
    )
    (net (code "24") (name "/PWM-CTRL-C") (class "Default")
      (node (ref "DD1") (pin "P$1") (pinfunction "PB12_P$1") (pintype "bidirectional"))
      (node (ref "SA12") (pin "1$O") (pinfunction "O_1$O") (pintype "passive"))
    )
    (net (code "27") (name "GND") (class "Default")
      (node (ref "C1") (pin "2") (pinfunction "2_2") (pintype "passive"))
      (node (ref "C10") (pin "2") (pinfunction "2_2") (pintype "passive"))
      (node (ref "C11") (pin "-") (pinfunction "-_-") (pintype "passive"))
      (node (ref "C12") (pin "-") (pinfunction "-_-") (pintype "passive"))
      (node (ref "C13") (pin "2") (pinfunction "2_2") (pintype "passive"))
      (node (ref "C14") (pin "2") (pinfunction "2_2") (pintype "passive"))
      (node (ref "C2") (pin "-") (pinfunction "-_-") (pintype "passive"))
      (node (ref "C3") (pin "-") (pinfunction "-_-") (pintype "passive"))
      (node (ref "C4") (pin "-") (pinfunction "-_-") (pintype "passive"))
      (node (ref "C5") (pin "2") (pinfunction "2_2") (pintype "passive"))
      (node (ref "C6") (pin "2") (pinfunction "2_2") (pintype "passive"))
      (node (ref "C7") (pin "-") (pinfunction "-_-") (pintype "passive"))
      (node (ref "C8") (pin "-") (pinfunction "-_-") (pintype "passive"))
      (node (ref "C9") (pin "2") (pinfunction "2_2") (pintype "passive"))
      (node (ref "DD1") (pin "P$19") (pinfunction "GND2_P$19") (pintype "bidirectional"))
      (node (ref "DD1") (pin "P$21") (pinfunction "GND1_P$21") (pintype "power_in"))
      (node (ref "DD1") (pin "P$22") (pinfunction "GND_P$22") (pintype "bidirectional"))
      (node (ref "HG2") (pin "P$7") (pinfunction "GND_P$7") (pintype "bidirectional"))
      (node (ref "HG2") (pin "P$9") (pinfunction "LED-K_P$9") (pintype "bidirectional"))
      (node (ref "J1") (pin "3") (pinfunction "3_3") (pintype "passive"))
      (node (ref "LED1") (pin "K") (pinfunction "C_K") (pintype "passive"))
      (node (ref "LED2") (pin "K") (pinfunction "C_K") (pintype "passive"))
      (node (ref "LED3") (pin "K") (pinfunction "C_K") (pintype "passive"))
      (node (ref "LED4") (pin "K") (pinfunction "C_K") (pintype "passive"))
      (node (ref "LED5") (pin "K") (pinfunction "C_K") (pintype "passive"))
      (node (ref "LED6") (pin "K") (pinfunction "C_K") (pintype "passive"))
      (node (ref "R15") (pin "1") (pinfunction "A_1") (pintype "passive"))
      (node (ref "R16") (pin "1") (pinfunction "A_1") (pintype "passive"))
      (node (ref "R2") (pin "1") (pinfunction "1_1") (pintype "passive"))
      (node (ref "R21") (pin "1") (pinfunction "1_1") (pintype "passive"))
      (node (ref "R22") (pin "1") (pinfunction "1_1") (pintype "passive"))
      (node (ref "R23") (pin "1") (pinfunction "1_1") (pintype "passive"))
      (node (ref "R24") (pin "1") (pinfunction "1_1") (pintype "passive"))
      (node (ref "R25") (pin "1") (pinfunction "1_1") (pintype "passive"))
      (node (ref "R27") (pin "2") (pinfunction "2_2") (pintype "passive"))
      (node (ref "R28") (pin "1") (pinfunction "1_1") (pintype "passive"))
      (node (ref "R42") (pin "1") (pinfunction "1_1") (pintype "passive"))
      (node (ref "R43") (pin "1") (pinfunction "1_1") (pintype "passive"))
      (node (ref "R44") (pin "1") (pinfunction "1_1") (pintype "passive"))
      (node (ref "R45") (pin "1") (pinfunction "A_1") (pintype "passive"))
      (node (ref "R46") (pin "1") (pinfunction "A_1") (pintype "passive"))
      (node (ref "R51") (pin "1") (pinfunction "1_1") (pintype "passive"))
      (node (ref "R52") (pin "1") (pinfunction "1_1") (pintype "passive"))
      (node (ref "R53") (pin "1") (pinfunction "1_1") (pintype "passive"))
      (node (ref "R54") (pin "1") (pinfunction "1_1") (pintype "passive"))
      (node (ref "R55") (pin "1") (pinfunction "1_1") (pintype "passive"))
      (node (ref "R57") (pin "2") (pinfunction "2_2") (pintype "passive"))
      (node (ref "R58") (pin "1") (pinfunction "1_1") (pintype "passive"))
      (node (ref "R72") (pin "1") (pinfunction "A_1") (pintype "passive"))
      (node (ref "R73") (pin "1") (pinfunction "A_1") (pintype "passive"))
      (node (ref "R78") (pin "1") (pinfunction "1_1") (pintype "passive"))
      (node (ref "R79") (pin "1") (pinfunction "1_1") (pintype "passive"))
      (node (ref "R80") (pin "1") (pinfunction "1_1") (pintype "passive"))
      (node (ref "R81") (pin "1") (pinfunction "1_1") (pintype "passive"))
      (node (ref "R82") (pin "1") (pinfunction "1_1") (pintype "passive"))
      (node (ref "R84") (pin "2") (pinfunction "2_2") (pintype "passive"))
      (node (ref "R85") (pin "1") (pinfunction "1_1") (pintype "passive"))
      (node (ref "SA11") (pin "P$3") (pinfunction "2_P$3") (pintype "passive"))
      (node (ref "SA11") (pin "P$4") (pinfunction "2_P$4") (pintype "passive"))
      (node (ref "SA14") (pin "1$S") (pinfunction "S_1$S") (pintype "passive"))
      (node (ref "SA16") (pin "P$3") (pinfunction "2_P$3") (pintype "passive"))
      (node (ref "SA16") (pin "P$4") (pinfunction "2_P$4") (pintype "passive"))
      (node (ref "SA4") (pin "1$S") (pinfunction "S_1$S") (pintype "passive"))
      (node (ref "SA6") (pin "P$3") (pinfunction "2_P$3") (pintype "passive"))
      (node (ref "SA6") (pin "P$4") (pinfunction "2_P$4") (pintype "passive"))
      (node (ref "SA9") (pin "1$S") (pinfunction "S_1$S") (pintype "passive"))
      (node (ref "VT10") (pin "3") (pinfunction "E_3") (pintype "passive"))
      (node (ref "VT11") (pin "3") (pinfunction "E_3") (pintype "passive"))
      (node (ref "VT12") (pin "3") (pinfunction "E_3") (pintype "passive"))
      (node (ref "VT17") (pin "3") (pinfunction "E_3") (pintype "passive"))
      (node (ref "VT18") (pin "3") (pinfunction "E_3") (pintype "passive"))
      (node (ref "VT19") (pin "3") (pinfunction "E_3") (pintype "passive"))
      (node (ref "VT3") (pin "3") (pinfunction "E_3") (pintype "passive"))
      (node (ref "VT4") (pin "3") (pinfunction "E_3") (pintype "passive"))
      (node (ref "VT5") (pin "3") (pinfunction "E_3") (pintype "passive"))
      (node (ref "XS7") (pin "P$2") (pinfunction "2_P$2") (pintype "passive"))
    )
    (net (code "28") (name "Net-(C5-Pad1)") (class "Default")
      (node (ref "C5") (pin "1") (pinfunction "1_1") (pintype "passive"))
      (node (ref "R17") (pin "2") (pinfunction "2_2") (pintype "passive"))
      (node (ref "R87") (pin "2") (pinfunction "2_2") (pintype "passive"))
      (node (ref "SA6") (pin "P$1") (pinfunction "1_P$1") (pintype "passive"))
      (node (ref "SA6") (pin "P$2") (pinfunction "1_P$2") (pintype "passive"))
    )
    (net (code "29") (name "Net-(C9-Pad1)") (class "Default")
      (node (ref "C9") (pin "1") (pinfunction "1_1") (pintype "passive"))
      (node (ref "R47") (pin "2") (pinfunction "2_2") (pintype "passive"))
      (node (ref "R88") (pin "2") (pinfunction "2_2") (pintype "passive"))
      (node (ref "SA11") (pin "P$1") (pinfunction "1_P$1") (pintype "passive"))
      (node (ref "SA11") (pin "P$2") (pinfunction "1_P$2") (pintype "passive"))
    )
    (net (code "30") (name "Net-(C13-Pad1)") (class "Default")
      (node (ref "C13") (pin "1") (pinfunction "1_1") (pintype "passive"))
      (node (ref "R74") (pin "2") (pinfunction "2_2") (pintype "passive"))
      (node (ref "R89") (pin "2") (pinfunction "2_2") (pintype "passive"))
      (node (ref "SA16") (pin "P$1") (pinfunction "1_P$1") (pintype "passive"))
      (node (ref "SA16") (pin "P$2") (pinfunction "1_P$2") (pintype "passive"))
    )
    (net (code "31") (name "Net-(D1-ANODE)") (class "Default")
      (node (ref "D1") (pin "A") (pinfunction "ANODE_A") (pintype "passive"))
      (node (ref "R5") (pin "1") (pinfunction "1_1") (pintype "passive"))
      (node (ref "R6") (pin "1") (pinfunction "1_1") (pintype "passive"))
      (node (ref "VT3") (pin "2") (pinfunction "B_2") (pintype "passive"))
      (node (ref "VT4") (pin "1") (pinfunction "C_1") (pintype "passive"))
    )
    (net (code "32") (name "Net-(D2-ANODE)") (class "Default")
      (node (ref "D2") (pin "A") (pinfunction "ANODE_A") (pintype "passive"))
      (node (ref "D3") (pin "A") (pinfunction "ANODE_A") (pintype "passive"))
      (node (ref "R7") (pin "1") (pinfunction "1_1") (pintype "passive"))
      (node (ref "VT5") (pin "2") (pinfunction "B_2") (pintype "passive"))
    )
    (net (code "33") (name "Net-(D4-ANODE)") (class "Default")
      (node (ref "C3") (pin "+") (pinfunction "+_+") (pintype "passive"))
      (node (ref "D4") (pin "A") (pinfunction "ANODE_A") (pintype "passive"))
      (node (ref "DA2") (pin "2") (pinfunction "VO_2") (pintype "passive"))
      (node (ref "R11") (pin "2") (pinfunction "2_2") (pintype "passive"))
    )
    (net (code "34") (name "Net-(D4-CATHODE)") (class "Default")
      (node (ref "D4") (pin "C") (pinfunction "CATHODE_C") (pintype "passive"))
      (node (ref "R10") (pin "1") (pinfunction "1_1") (pintype "passive"))
      (node (ref "R10") (pin "3") (pinfunction "1_3") (pintype "passive"))
      (node (ref "VT6") (pin "3") (pinfunction "D_3") (pintype "passive"))
    )
    (net (code "35") (name "Net-(D5-ANODE)") (class "Default")
      (node (ref "C4") (pin "+") (pinfunction "+_+") (pintype "passive"))
      (node (ref "D5") (pin "A") (pinfunction "ANODE_A") (pintype "passive"))
      (node (ref "DA3") (pin "2") (pinfunction "VO_2") (pintype "passive"))
      (node (ref "R13") (pin "2") (pinfunction "2_2") (pintype "passive"))
    )
    (net (code "36") (name "Net-(D5-CATHODE)") (class "Default")
      (node (ref "D5") (pin "C") (pinfunction "CATHODE_C") (pintype "passive"))
      (node (ref "VT7") (pin "3") (pinfunction "D_3") (pintype "passive"))
      (node (ref "XS1") (pin "P$1") (pinfunction "1_P$1") (pintype "passive"))
      (node (ref "XS2") (pin "1") (pinfunction "1_1") (pintype "passive"))
    )
    (net (code "37") (name "Net-(D6-ANODE)") (class "Default")
      (node (ref "D6") (pin "A") (pinfunction "ANODE_A") (pintype "passive"))
      (node (ref "R32") (pin "1") (pinfunction "1_1") (pintype "passive"))
      (node (ref "R33") (pin "1") (pinfunction "1_1") (pintype "passive"))
      (node (ref "VT10") (pin "2") (pinfunction "B_2") (pintype "passive"))
      (node (ref "VT11") (pin "1") (pinfunction "C_1") (pintype "passive"))
    )
    (net (code "38") (name "Net-(D7-ANODE)") (class "Default")
      (node (ref "D7") (pin "A") (pinfunction "ANODE_A") (pintype "passive"))
      (node (ref "D8") (pin "A") (pinfunction "ANODE_A") (pintype "passive"))
      (node (ref "R34") (pin "1") (pinfunction "1_1") (pintype "passive"))
      (node (ref "VT12") (pin "2") (pinfunction "B_2") (pintype "passive"))
    )
    (net (code "39") (name "Net-(D9-ANODE)") (class "Default")
      (node (ref "C7") (pin "+") (pinfunction "+_+") (pintype "passive"))
      (node (ref "D9") (pin "A") (pinfunction "ANODE_A") (pintype "passive"))
      (node (ref "DA4") (pin "2") (pinfunction "VO_2") (pintype "passive"))
      (node (ref "R38") (pin "2") (pinfunction "2_2") (pintype "passive"))
    )
    (net (code "40") (name "Net-(D9-CATHODE)") (class "Default")
      (node (ref "D9") (pin "C") (pinfunction "CATHODE_C") (pintype "passive"))
      (node (ref "R37") (pin "1") (pinfunction "1_1") (pintype "passive"))
      (node (ref "R37") (pin "3") (pinfunction "1_3") (pintype "passive"))
      (node (ref "VT13") (pin "3") (pinfunction "D_3") (pintype "passive"))
    )
    (net (code "41") (name "Net-(D10-ANODE)") (class "Default")
      (node (ref "C8") (pin "+") (pinfunction "+_+") (pintype "passive"))
      (node (ref "D10") (pin "A") (pinfunction "ANODE_A") (pintype "passive"))
      (node (ref "DA5") (pin "2") (pinfunction "VO_2") (pintype "passive"))
      (node (ref "R40") (pin "2") (pinfunction "2_2") (pintype "passive"))
    )
    (net (code "42") (name "Net-(D10-CATHODE)") (class "Default")
      (node (ref "D10") (pin "C") (pinfunction "CATHODE_C") (pintype "passive"))
      (node (ref "VT14") (pin "3") (pinfunction "D_3") (pintype "passive"))
      (node (ref "XS3") (pin "P$1") (pinfunction "1_P$1") (pintype "passive"))
      (node (ref "XS4") (pin "1") (pinfunction "1_1") (pintype "passive"))
    )
    (net (code "43") (name "Net-(D11-ANODE)") (class "Default")
      (node (ref "D11") (pin "A") (pinfunction "ANODE_A") (pintype "passive"))
      (node (ref "R62") (pin "1") (pinfunction "1_1") (pintype "passive"))
      (node (ref "R63") (pin "1") (pinfunction "1_1") (pintype "passive"))
      (node (ref "VT17") (pin "2") (pinfunction "B_2") (pintype "passive"))
      (node (ref "VT18") (pin "1") (pinfunction "C_1") (pintype "passive"))
    )
    (net (code "44") (name "Net-(D12-ANODE)") (class "Default")
      (node (ref "D12") (pin "A") (pinfunction "ANODE_A") (pintype "passive"))
      (node (ref "D13") (pin "A") (pinfunction "ANODE_A") (pintype "passive"))
      (node (ref "R64") (pin "1") (pinfunction "1_1") (pintype "passive"))
      (node (ref "VT19") (pin "2") (pinfunction "B_2") (pintype "passive"))
    )
    (net (code "45") (name "Net-(D14-ANODE)") (class "Default")
      (node (ref "C11") (pin "+") (pinfunction "+_+") (pintype "passive"))
      (node (ref "D14") (pin "A") (pinfunction "ANODE_A") (pintype "passive"))
      (node (ref "DA6") (pin "2") (pinfunction "VO_2") (pintype "passive"))
      (node (ref "R68") (pin "2") (pinfunction "2_2") (pintype "passive"))
    )
    (net (code "46") (name "Net-(D14-CATHODE)") (class "Default")
      (node (ref "D14") (pin "C") (pinfunction "CATHODE_C") (pintype "passive"))
      (node (ref "R67") (pin "1") (pinfunction "1_1") (pintype "passive"))
      (node (ref "R67") (pin "3") (pinfunction "1_3") (pintype "passive"))
      (node (ref "VT20") (pin "3") (pinfunction "D_3") (pintype "passive"))
    )
    (net (code "47") (name "Net-(D15-ANODE)") (class "Default")
      (node (ref "C12") (pin "+") (pinfunction "+_+") (pintype "passive"))
      (node (ref "D15") (pin "A") (pinfunction "ANODE_A") (pintype "passive"))
      (node (ref "DA7") (pin "2") (pinfunction "VO_2") (pintype "passive"))
      (node (ref "R70") (pin "2") (pinfunction "2_2") (pintype "passive"))
    )
    (net (code "48") (name "Net-(D15-CATHODE)") (class "Default")
      (node (ref "D15") (pin "C") (pinfunction "CATHODE_C") (pintype "passive"))
      (node (ref "VT21") (pin "3") (pinfunction "D_3") (pintype "passive"))
      (node (ref "XS5") (pin "P$1") (pinfunction "1_P$1") (pintype "passive"))
      (node (ref "XS6") (pin "1") (pinfunction "1_1") (pintype "passive"))
    )
    (net (code "49") (name "Net-(DA1-ADJ)") (class "Default")
      (node (ref "DA1") (pin "1") (pinfunction "ADJ_1") (pintype "passive"))
      (node (ref "R1") (pin "1") (pinfunction "1_1") (pintype "passive"))
      (node (ref "R2") (pin "2") (pinfunction "2_2") (pintype "passive"))
    )
    (net (code "50") (name "Net-(DA2-ADJ)") (class "Default")
      (node (ref "DA2") (pin "1") (pinfunction "ADJ_1") (pintype "passive"))
      (node (ref "R15") (pin "2") (pinfunction "S_2") (pintype "passive"))
    )
    (net (code "51") (name "Net-(DA2-VI)") (class "Default")
      (node (ref "DA2") (pin "3") (pinfunction "VI_3") (pintype "input"))
      (node (ref "R12") (pin "2") (pinfunction "2_2") (pintype "passive"))
      (node (ref "R20") (pin "1") (pinfunction "1_1") (pintype "passive"))
      (node (ref "VT1") (pin "3") (pinfunction "D_3") (pintype "passive"))
    )
    (net (code "52") (name "Net-(DA3-ADJ)") (class "Default")
      (node (ref "DA3") (pin "1") (pinfunction "ADJ_1") (pintype "passive"))
      (node (ref "R16") (pin "2") (pinfunction "S_2") (pintype "passive"))
    )
    (net (code "53") (name "Net-(DA3-VI)") (class "Default")
      (node (ref "DA3") (pin "3") (pinfunction "VI_3") (pintype "input"))
      (node (ref "R14") (pin "2") (pinfunction "2_2") (pintype "passive"))
      (node (ref "R18") (pin "2") (pinfunction "2_2") (pintype "passive"))
      (node (ref "VT2") (pin "3") (pinfunction "D_3") (pintype "passive"))
    )
    (net (code "54") (name "Net-(DA4-ADJ)") (class "Default")
      (node (ref "DA4") (pin "1") (pinfunction "ADJ_1") (pintype "passive"))
      (node (ref "R45") (pin "2") (pinfunction "S_2") (pintype "passive"))
    )
    (net (code "55") (name "Net-(DA4-VI)") (class "Default")
      (node (ref "DA4") (pin "3") (pinfunction "VI_3") (pintype "input"))
      (node (ref "R39") (pin "2") (pinfunction "2_2") (pintype "passive"))
      (node (ref "R50") (pin "1") (pinfunction "1_1") (pintype "passive"))
      (node (ref "VT8") (pin "3") (pinfunction "D_3") (pintype "passive"))
    )
    (net (code "56") (name "Net-(DA5-ADJ)") (class "Default")
      (node (ref "DA5") (pin "1") (pinfunction "ADJ_1") (pintype "passive"))
      (node (ref "R46") (pin "2") (pinfunction "S_2") (pintype "passive"))
    )
    (net (code "57") (name "Net-(DA5-VI)") (class "Default")
      (node (ref "DA5") (pin "3") (pinfunction "VI_3") (pintype "input"))
      (node (ref "R41") (pin "2") (pinfunction "2_2") (pintype "passive"))
      (node (ref "R48") (pin "2") (pinfunction "2_2") (pintype "passive"))
      (node (ref "VT9") (pin "3") (pinfunction "D_3") (pintype "passive"))
    )
    (net (code "58") (name "Net-(DA6-ADJ)") (class "Default")
      (node (ref "DA6") (pin "1") (pinfunction "ADJ_1") (pintype "passive"))
      (node (ref "R72") (pin "2") (pinfunction "S_2") (pintype "passive"))
    )
    (net (code "59") (name "Net-(DA6-VI)") (class "Default")
      (node (ref "DA6") (pin "3") (pinfunction "VI_3") (pintype "input"))
      (node (ref "R69") (pin "2") (pinfunction "2_2") (pintype "passive"))
      (node (ref "R77") (pin "1") (pinfunction "1_1") (pintype "passive"))
      (node (ref "VT15") (pin "3") (pinfunction "D_3") (pintype "passive"))
    )
    (net (code "60") (name "Net-(DA7-ADJ)") (class "Default")
      (node (ref "DA7") (pin "1") (pinfunction "ADJ_1") (pintype "passive"))
      (node (ref "R73") (pin "2") (pinfunction "S_2") (pintype "passive"))
    )
    (net (code "61") (name "Net-(DA7-VI)") (class "Default")
      (node (ref "DA7") (pin "3") (pinfunction "VI_3") (pintype "input"))
      (node (ref "R71") (pin "2") (pinfunction "2_2") (pintype "passive"))
      (node (ref "R75") (pin "2") (pinfunction "2_2") (pintype "passive"))
      (node (ref "VT16") (pin "3") (pinfunction "D_3") (pintype "passive"))
    )
    (net (code "62") (name "Net-(DD1-PA8)") (class "Default")
      (node (ref "DD1") (pin "P$5") (pinfunction "PA8_P$5") (pintype "bidirectional"))
      (node (ref "JP1") (pin "3") (pinfunction "3_3") (pintype "passive"))
    )
    (net (code "63") (name "Net-(DD1-PA9)") (class "Default")
      (node (ref "DD1") (pin "P$6") (pinfunction "PA9_P$6") (pintype "bidirectional"))
      (node (ref "JP1") (pin "2") (pinfunction "2_2") (pintype "passive"))
    )
    (net (code "64") (name "Net-(DD1-PA10)") (class "Default")
      (node (ref "DD1") (pin "P$7") (pinfunction "PA10_P$7") (pintype "bidirectional"))
      (node (ref "JP1") (pin "1") (pinfunction "1_1") (pintype "passive"))
    )
    (net (code "65") (name "Net-(DD1-PB5)") (class "Default")
      (node (ref "DD1") (pin "P$13") (pinfunction "PB5_P$13") (pintype "bidirectional"))
      (node (ref "HG2") (pin "P$1") (pinfunction "CS_P$1") (pintype "bidirectional"))
    )
    (net (code "66") (name "Net-(DD1-PB6)") (class "Default")
      (node (ref "DD1") (pin "P$14") (pinfunction "PB6_P$14") (pintype "bidirectional"))
      (node (ref "HG2") (pin "P$2") (pinfunction "RST_P$2") (pintype "bidirectional"))
    )
    (net (code "67") (name "Net-(DD1-PB7)") (class "Default")
      (node (ref "DD1") (pin "P$15") (pinfunction "PB7_P$15") (pintype "bidirectional"))
      (node (ref "HG2") (pin "P$3") (pinfunction "RS_P$3") (pintype "bidirectional"))
    )
    (net (code "68") (name "Net-(DD1-PB8)") (class "Default")
      (node (ref "DD1") (pin "P$16") (pinfunction "PB8_P$16") (pintype "bidirectional"))
      (node (ref "HG2") (pin "P$4") (pinfunction "SCK_P$4") (pintype "bidirectional"))
    )
    (net (code "69") (name "Net-(DD1-PB9)") (class "Default")
      (node (ref "DD1") (pin "P$17") (pinfunction "PB9_P$17") (pintype "bidirectional"))
      (node (ref "HG2") (pin "P$5") (pinfunction "SDA_P$5") (pintype "bidirectional"))
    )
    (net (code "70") (name "Net-(F1-Pad1)") (class "Default")
      (node (ref "F1") (pin "1") (pinfunction "1_1") (pintype "passive"))
      (node (ref "J1") (pin "1") (pinfunction "1_1") (pintype "passive"))
    )
    (net (code "71") (name "Net-(IC1A-+IN)") (class "Default")
      (node (ref "IC1") (pin "3") (pinfunction "+IN_3") (pintype "input"))
      (node (ref "R25") (pin "2") (pinfunction "2_2") (pintype "passive"))
      (node (ref "VT7") (pin "2") (pinfunction "S_2") (pintype "passive"))
    )
    (net (code "72") (name "Net-(IC1A--IN)") (class "Default")
      (node (ref "IC1") (pin "2") (pinfunction "-IN_2") (pintype "input"))
      (node (ref "R28") (pin "2") (pinfunction "2_2") (pintype "passive"))
      (node (ref "R29") (pin "1") (pinfunction "1_1") (pintype "passive"))
    )
    (net (code "73") (name "Net-(IC1B-+IN)") (class "Default")
      (node (ref "IC1") (pin "5") (pinfunction "+IN_5") (pintype "input"))
      (node (ref "R24") (pin "2") (pinfunction "2_2") (pintype "passive"))
      (node (ref "VT6") (pin "2") (pinfunction "S_2") (pintype "passive"))
    )
    (net (code "74") (name "Net-(IC1B--IN)") (class "Default")
      (node (ref "IC1") (pin "6") (pinfunction "-IN_6") (pintype "input"))
      (node (ref "R26") (pin "2") (pinfunction "2_2") (pintype "passive"))
      (node (ref "R27") (pin "1") (pinfunction "1_1") (pintype "passive"))
    )
    (net (code "75") (name "Net-(IC2A-+IN)") (class "Default")
      (node (ref "IC2") (pin "3") (pinfunction "+IN_3") (pintype "input"))
      (node (ref "R55") (pin "2") (pinfunction "2_2") (pintype "passive"))
      (node (ref "VT14") (pin "2") (pinfunction "S_2") (pintype "passive"))
    )
    (net (code "76") (name "Net-(IC2A--IN)") (class "Default")
      (node (ref "IC2") (pin "2") (pinfunction "-IN_2") (pintype "input"))
      (node (ref "R58") (pin "2") (pinfunction "2_2") (pintype "passive"))
      (node (ref "R59") (pin "1") (pinfunction "1_1") (pintype "passive"))
    )
    (net (code "77") (name "Net-(IC2B-+IN)") (class "Default")
      (node (ref "IC2") (pin "5") (pinfunction "+IN_5") (pintype "input"))
      (node (ref "R54") (pin "2") (pinfunction "2_2") (pintype "passive"))
      (node (ref "VT13") (pin "2") (pinfunction "S_2") (pintype "passive"))
    )
    (net (code "78") (name "Net-(IC2B--IN)") (class "Default")
      (node (ref "IC2") (pin "6") (pinfunction "-IN_6") (pintype "input"))
      (node (ref "R56") (pin "2") (pinfunction "2_2") (pintype "passive"))
      (node (ref "R57") (pin "1") (pinfunction "1_1") (pintype "passive"))
    )
    (net (code "79") (name "Net-(IC3A-+IN)") (class "Default")
      (node (ref "IC3") (pin "3") (pinfunction "+IN_3") (pintype "input"))
      (node (ref "R82") (pin "2") (pinfunction "2_2") (pintype "passive"))
      (node (ref "VT21") (pin "2") (pinfunction "S_2") (pintype "passive"))
    )
    (net (code "80") (name "Net-(IC3A--IN)") (class "Default")
      (node (ref "IC3") (pin "2") (pinfunction "-IN_2") (pintype "input"))
      (node (ref "R85") (pin "2") (pinfunction "2_2") (pintype "passive"))
      (node (ref "R86") (pin "1") (pinfunction "1_1") (pintype "passive"))
    )
    (net (code "81") (name "Net-(IC3B-+IN)") (class "Default")
      (node (ref "IC3") (pin "5") (pinfunction "+IN_5") (pintype "input"))
      (node (ref "R81") (pin "2") (pinfunction "2_2") (pintype "passive"))
      (node (ref "VT20") (pin "2") (pinfunction "S_2") (pintype "passive"))
    )
    (net (code "82") (name "Net-(IC3B--IN)") (class "Default")
      (node (ref "IC3") (pin "6") (pinfunction "-IN_6") (pintype "input"))
      (node (ref "R83") (pin "2") (pinfunction "2_2") (pintype "passive"))
      (node (ref "R84") (pin "1") (pinfunction "1_1") (pintype "passive"))
    )
    (net (code "83") (name "Net-(LED1-PadA)") (class "Default")
      (node (ref "LED1") (pin "A") (pinfunction "A_A") (pintype "passive"))
      (node (ref "R12") (pin "1") (pinfunction "1_1") (pintype "passive"))
    )
    (net (code "84") (name "Net-(LED2-PadA)") (class "Default")
      (node (ref "LED2") (pin "A") (pinfunction "A_A") (pintype "passive"))
      (node (ref "R14") (pin "1") (pinfunction "1_1") (pintype "passive"))
    )
    (net (code "85") (name "Net-(LED3-PadA)") (class "Default")
      (node (ref "LED3") (pin "A") (pinfunction "A_A") (pintype "passive"))
      (node (ref "R39") (pin "1") (pinfunction "1_1") (pintype "passive"))
    )
    (net (code "86") (name "Net-(LED4-PadA)") (class "Default")
      (node (ref "LED4") (pin "A") (pinfunction "A_A") (pintype "passive"))
      (node (ref "R41") (pin "1") (pinfunction "1_1") (pintype "passive"))
    )
    (net (code "87") (name "Net-(LED5-PadA)") (class "Default")
      (node (ref "LED5") (pin "A") (pinfunction "A_A") (pintype "passive"))
      (node (ref "R69") (pin "1") (pinfunction "1_1") (pintype "passive"))
    )
    (net (code "88") (name "Net-(LED6-PadA)") (class "Default")
      (node (ref "LED6") (pin "A") (pinfunction "A_A") (pintype "passive"))
      (node (ref "R71") (pin "1") (pinfunction "1_1") (pintype "passive"))
    )
    (net (code "89") (name "Net-(R10B-2)") (class "Default")
      (node (ref "R10") (pin "4") (pinfunction "2_4") (pintype "passive"))
      (node (ref "SA5") (pin "1$P") (pinfunction "P_1$P") (pintype "passive"))
    )
    (net (code "90") (name "Net-(R15-E)") (class "Default")
      (node (ref "R11") (pin "1") (pinfunction "1_1") (pintype "passive"))
      (node (ref "R15") (pin "3") (pinfunction "E_3") (pintype "passive"))
    )
    (net (code "91") (name "Net-(R16-E)") (class "Default")
      (node (ref "R13") (pin "1") (pinfunction "1_1") (pintype "passive"))
      (node (ref "R16") (pin "3") (pinfunction "E_3") (pintype "passive"))
    )
    (net (code "92") (name "Net-(R19-Pad1)") (class "Default")
      (node (ref "R19") (pin "1") (pinfunction "1_1") (pintype "passive"))
      (node (ref "R21") (pin "2") (pinfunction "2_2") (pintype "passive"))
    )
    (net (code "93") (name "Net-(R37B-2)") (class "Default")
      (node (ref "R37") (pin "4") (pinfunction "2_4") (pintype "passive"))
      (node (ref "SA10") (pin "1$P") (pinfunction "P_1$P") (pintype "passive"))
    )
    (net (code "94") (name "Net-(R45-E)") (class "Default")
      (node (ref "R38") (pin "1") (pinfunction "1_1") (pintype "passive"))
      (node (ref "R45") (pin "3") (pinfunction "E_3") (pintype "passive"))
    )
    (net (code "95") (name "Net-(R46-E)") (class "Default")
      (node (ref "R40") (pin "1") (pinfunction "1_1") (pintype "passive"))
      (node (ref "R46") (pin "3") (pinfunction "E_3") (pintype "passive"))
    )
    (net (code "96") (name "Net-(R49-Pad1)") (class "Default")
      (node (ref "R49") (pin "1") (pinfunction "1_1") (pintype "passive"))
      (node (ref "R51") (pin "2") (pinfunction "2_2") (pintype "passive"))
    )
    (net (code "97") (name "Net-(R67B-2)") (class "Default")
      (node (ref "R67") (pin "4") (pinfunction "2_4") (pintype "passive"))
      (node (ref "SA15") (pin "1$P") (pinfunction "P_1$P") (pintype "passive"))
    )
    (net (code "98") (name "Net-(R72-E)") (class "Default")
      (node (ref "R68") (pin "1") (pinfunction "1_1") (pintype "passive"))
      (node (ref "R72") (pin "3") (pinfunction "E_3") (pintype "passive"))
    )
    (net (code "99") (name "Net-(R73-E)") (class "Default")
      (node (ref "R70") (pin "1") (pinfunction "1_1") (pintype "passive"))
      (node (ref "R73") (pin "3") (pinfunction "E_3") (pintype "passive"))
    )
    (net (code "100") (name "Net-(R76-Pad1)") (class "Default")
      (node (ref "R76") (pin "1") (pinfunction "1_1") (pintype "passive"))
      (node (ref "R78") (pin "2") (pinfunction "2_2") (pintype "passive"))
    )
    (net (code "101") (name "Net-(SA1-P)") (class "Default")
      (node (ref "F1") (pin "2") (pinfunction "2_2") (pintype "passive"))
      (node (ref "SA1") (pin "3") (pinfunction "P_3") (pintype "passive"))
    )
    (net (code "102") (name "Net-(SA2-S)") (class "Default")
      (node (ref "C6") (pin "1") (pinfunction "1_1") (pintype "passive"))
      (node (ref "SA2") (pin "1$S") (pinfunction "S_1$S") (pintype "passive"))
      (node (ref "SA4") (pin "1$P") (pinfunction "P_1$P") (pintype "passive"))
    )
    (net (code "103") (name "Net-(SA3-P)") (class "Default")
      (node (ref "R10") (pin "2") (pinfunction "2_2") (pintype "passive"))
      (node (ref "SA3") (pin "1$P") (pinfunction "P_1$P") (pintype "passive"))
    )
    (net (code "104") (name "Net-(SA3-S)") (class "Default")
      (node (ref "SA3") (pin "1$S") (pinfunction "S_1$S") (pintype "passive"))
      (node (ref "SA5") (pin "1$S") (pinfunction "S_1$S") (pintype "passive"))
      (node (ref "XS1") (pin "P$2") (pinfunction "2_P$2") (pintype "passive"))
      (node (ref "XS2") (pin "2") (pinfunction "2_2") (pintype "passive"))
    )
    (net (code "105") (name "Net-(SA4-O)") (class "Default")
      (node (ref "R8") (pin "1") (pinfunction "1_1") (pintype "passive"))
      (node (ref "SA4") (pin "1$O") (pinfunction "O_1$O") (pintype "passive"))
    )
    (net (code "106") (name "Net-(SA7-S)") (class "Default")
      (node (ref "C10") (pin "1") (pinfunction "1_1") (pintype "passive"))
      (node (ref "SA7") (pin "1$S") (pinfunction "S_1$S") (pintype "passive"))
      (node (ref "SA9") (pin "1$P") (pinfunction "P_1$P") (pintype "passive"))
    )
    (net (code "107") (name "Net-(SA8-P)") (class "Default")
      (node (ref "R37") (pin "2") (pinfunction "2_2") (pintype "passive"))
      (node (ref "SA8") (pin "1$P") (pinfunction "P_1$P") (pintype "passive"))
    )
    (net (code "108") (name "Net-(SA9-O)") (class "Default")
      (node (ref "R35") (pin "1") (pinfunction "1_1") (pintype "passive"))
      (node (ref "SA9") (pin "1$O") (pinfunction "O_1$O") (pintype "passive"))
    )
    (net (code "109") (name "Net-(SA10-S)") (class "Default")
      (node (ref "SA10") (pin "1$S") (pinfunction "S_1$S") (pintype "passive"))
      (node (ref "SA8") (pin "1$S") (pinfunction "S_1$S") (pintype "passive"))
      (node (ref "XS3") (pin "P$2") (pinfunction "2_P$2") (pintype "passive"))
      (node (ref "XS4") (pin "2") (pinfunction "2_2") (pintype "passive"))
    )
    (net (code "110") (name "Net-(SA12-S)") (class "Default")
      (node (ref "C14") (pin "1") (pinfunction "1_1") (pintype "passive"))
      (node (ref "SA12") (pin "1$S") (pinfunction "S_1$S") (pintype "passive"))
      (node (ref "SA14") (pin "1$P") (pinfunction "P_1$P") (pintype "passive"))
    )
    (net (code "111") (name "Net-(SA13-P)") (class "Default")
      (node (ref "R67") (pin "2") (pinfunction "2_2") (pintype "passive"))
      (node (ref "SA13") (pin "1$P") (pinfunction "P_1$P") (pintype "passive"))
    )
    (net (code "112") (name "Net-(SA13-S)") (class "Default")
      (node (ref "SA13") (pin "1$S") (pinfunction "S_1$S") (pintype "passive"))
      (node (ref "SA15") (pin "1$S") (pinfunction "S_1$S") (pintype "passive"))
      (node (ref "XS5") (pin "P$2") (pinfunction "2_P$2") (pintype "passive"))
      (node (ref "XS6") (pin "2") (pinfunction "2_2") (pintype "passive"))
    )
    (net (code "113") (name "Net-(SA14-O)") (class "Default")
      (node (ref "R65") (pin "1") (pinfunction "1_1") (pintype "passive"))
      (node (ref "SA14") (pin "1$O") (pinfunction "O_1$O") (pintype "passive"))
    )
    (net (code "114") (name "Net-(VT1-G)") (class "Default")
      (node (ref "R3") (pin "1") (pinfunction "1_1") (pintype "passive"))
      (node (ref "VT1") (pin "1") (pinfunction "G_1") (pintype "passive"))
      (node (ref "VT3") (pin "1") (pinfunction "C_1") (pintype "passive"))
    )
    (net (code "115") (name "Net-(VT2-G)") (class "Default")
      (node (ref "R4") (pin "1") (pinfunction "1_1") (pintype "passive"))
      (node (ref "VT2") (pin "1") (pinfunction "G_1") (pintype "passive"))
      (node (ref "VT5") (pin "1") (pinfunction "C_1") (pintype "passive"))
    )
    (net (code "116") (name "Net-(VT4-B)") (class "Default")
      (node (ref "R9") (pin "1") (pinfunction "1_1") (pintype "passive"))
      (node (ref "VT4") (pin "2") (pinfunction "B_2") (pintype "passive"))
    )
    (net (code "117") (name "Net-(VT6-G)") (class "Default")
      (node (ref "R18") (pin "1") (pinfunction "1_1") (pintype "passive"))
      (node (ref "R22") (pin "2") (pinfunction "2_2") (pintype "passive"))
      (node (ref "VT6") (pin "1") (pinfunction "G_1") (pintype "passive"))
    )
    (net (code "118") (name "Net-(VT7-G)") (class "Default")
      (node (ref "R20") (pin "2") (pinfunction "2_2") (pintype "passive"))
      (node (ref "R23") (pin "2") (pinfunction "2_2") (pintype "passive"))
      (node (ref "VT7") (pin "1") (pinfunction "G_1") (pintype "passive"))
    )
    (net (code "119") (name "Net-(VT10-C)") (class "Default")
      (node (ref "R30") (pin "1") (pinfunction "1_1") (pintype "passive"))
      (node (ref "VT10") (pin "1") (pinfunction "C_1") (pintype "passive"))
      (node (ref "VT8") (pin "1") (pinfunction "G_1") (pintype "passive"))
    )
    (net (code "120") (name "Net-(VT11-B)") (class "Default")
      (node (ref "R36") (pin "1") (pinfunction "1_1") (pintype "passive"))
      (node (ref "VT11") (pin "2") (pinfunction "B_2") (pintype "passive"))
    )
    (net (code "121") (name "Net-(VT12-C)") (class "Default")
      (node (ref "R31") (pin "1") (pinfunction "1_1") (pintype "passive"))
      (node (ref "VT12") (pin "1") (pinfunction "C_1") (pintype "passive"))
      (node (ref "VT9") (pin "1") (pinfunction "G_1") (pintype "passive"))
    )
    (net (code "122") (name "Net-(VT13-G)") (class "Default")
      (node (ref "R48") (pin "1") (pinfunction "1_1") (pintype "passive"))
      (node (ref "R52") (pin "2") (pinfunction "2_2") (pintype "passive"))
      (node (ref "VT13") (pin "1") (pinfunction "G_1") (pintype "passive"))
    )
    (net (code "123") (name "Net-(VT14-G)") (class "Default")
      (node (ref "R50") (pin "2") (pinfunction "2_2") (pintype "passive"))
      (node (ref "R53") (pin "2") (pinfunction "2_2") (pintype "passive"))
      (node (ref "VT14") (pin "1") (pinfunction "G_1") (pintype "passive"))
    )
    (net (code "124") (name "Net-(VT15-G)") (class "Default")
      (node (ref "R60") (pin "1") (pinfunction "1_1") (pintype "passive"))
      (node (ref "VT15") (pin "1") (pinfunction "G_1") (pintype "passive"))
      (node (ref "VT17") (pin "1") (pinfunction "C_1") (pintype "passive"))
    )
    (net (code "125") (name "Net-(VT16-G)") (class "Default")
      (node (ref "R61") (pin "1") (pinfunction "1_1") (pintype "passive"))
      (node (ref "VT16") (pin "1") (pinfunction "G_1") (pintype "passive"))
      (node (ref "VT19") (pin "1") (pinfunction "C_1") (pintype "passive"))
    )
    (net (code "126") (name "Net-(VT18-B)") (class "Default")
      (node (ref "R66") (pin "1") (pinfunction "1_1") (pintype "passive"))
      (node (ref "VT18") (pin "2") (pinfunction "B_2") (pintype "passive"))
    )
    (net (code "127") (name "Net-(VT20-G)") (class "Default")
      (node (ref "R75") (pin "1") (pinfunction "1_1") (pintype "passive"))
      (node (ref "R79") (pin "2") (pinfunction "2_2") (pintype "passive"))
      (node (ref "VT20") (pin "1") (pinfunction "G_1") (pintype "passive"))
    )
    (net (code "128") (name "Net-(VT21-G)") (class "Default")
      (node (ref "R77") (pin "2") (pinfunction "2_2") (pintype "passive"))
      (node (ref "R80") (pin "2") (pinfunction "2_2") (pintype "passive"))
      (node (ref "VT21") (pin "1") (pinfunction "G_1") (pintype "passive"))
    )
    (net (code "129") (name "VCC") (class "Default")
      (node (ref "C2") (pin "+") (pinfunction "+_+") (pintype "passive"))
      (node (ref "DA1") (pin "2") (pinfunction "VO_2") (pintype "passive"))
      (node (ref "DD1") (pin "P$20") (pinfunction "3.3V1_P$20") (pintype "bidirectional"))
      (node (ref "DD1") (pin "P$23") (pinfunction "3.3V_P$23") (pintype "bidirectional"))
      (node (ref "HG2") (pin "P$6") (pinfunction "VCC_P$6") (pintype "bidirectional"))
      (node (ref "HG2") (pin "P$8") (pinfunction "LED-A_P$8") (pintype "bidirectional"))
      (node (ref "R1") (pin "2") (pinfunction "2_2") (pintype "passive"))
      (node (ref "R17") (pin "1") (pinfunction "1_1") (pintype "passive"))
      (node (ref "R19") (pin "3") (pinfunction "2_3") (pintype "passive"))
      (node (ref "R32") (pin "2") (pinfunction "2_2") (pintype "passive"))
      (node (ref "R33") (pin "2") (pinfunction "2_2") (pintype "passive"))
      (node (ref "R34") (pin "2") (pinfunction "2_2") (pintype "passive"))
      (node (ref "R35") (pin "2") (pinfunction "2_2") (pintype "passive"))
      (node (ref "R47") (pin "1") (pinfunction "1_1") (pintype "passive"))
      (node (ref "R49") (pin "3") (pinfunction "2_3") (pintype "passive"))
      (node (ref "R5") (pin "2") (pinfunction "2_2") (pintype "passive"))
      (node (ref "R6") (pin "2") (pinfunction "2_2") (pintype "passive"))
      (node (ref "R62") (pin "2") (pinfunction "2_2") (pintype "passive"))
      (node (ref "R63") (pin "2") (pinfunction "2_2") (pintype "passive"))
      (node (ref "R64") (pin "2") (pinfunction "2_2") (pintype "passive"))
      (node (ref "R65") (pin "2") (pinfunction "2_2") (pintype "passive"))
      (node (ref "R7") (pin "2") (pinfunction "2_2") (pintype "passive"))
      (node (ref "R74") (pin "1") (pinfunction "1_1") (pintype "passive"))
      (node (ref "R76") (pin "3") (pinfunction "2_3") (pintype "passive"))
      (node (ref "R8") (pin "2") (pinfunction "2_2") (pintype "passive"))
      (node (ref "S1") (pin "4") (pinfunction "4_4") (pintype "passive"))
      (node (ref "S1") (pin "5") (pinfunction "5_5") (pintype "passive"))
      (node (ref "S1") (pin "6") (pinfunction "6_6") (pintype "passive"))
    )
    (net (code "130") (name "unconnected-(DD1-5V-PadP$18)") (class "Default")
      (node (ref "DD1") (pin "P$18") (pinfunction "5V_P$18") (pintype "bidirectional"))
    )
    (net (code "131") (name "unconnected-(DD1-PC13-PadP$39)") (class "Default")
      (node (ref "DD1") (pin "P$39") (pinfunction "PC13_P$39") (pintype "bidirectional"))
    )
    (net (code "132") (name "unconnected-(DD1-PC14-PadP$38)") (class "Default")
      (node (ref "DD1") (pin "P$38") (pinfunction "PC14_P$38") (pintype "bidirectional"))
    )
    (net (code "133") (name "unconnected-(DD1-PC15-PadP$37)") (class "Default")
      (node (ref "DD1") (pin "P$37") (pinfunction "PC15_P$37") (pintype "bidirectional"))
    )
    (net (code "134") (name "unconnected-(DD1-RESET-PadP$24)") (class "Default")
      (node (ref "DD1") (pin "P$24") (pinfunction "RESET_P$24") (pintype "bidirectional"))
    )
    (net (code "135") (name "unconnected-(DD1-VBAT-PadP$40)") (class "Default")
      (node (ref "DD1") (pin "P$40") (pinfunction "VBAT_P$40") (pintype "bidirectional"))
    )
    (net (code "136") (name "unconnected-(J1-Pad2)") (class "Default")
      (node (ref "J1") (pin "2") (pinfunction "2_2") (pintype "passive"))
    )
    (net (code "137") (name "unconnected-(SA1-S-Pad2)") (class "Default")
      (node (ref "SA1") (pin "2") (pinfunction "S_2") (pintype "passive"))
    )
    (net (code "138") (name "unconnected-(SA3-O-Pad1$O)") (class "Default")
      (node (ref "SA3") (pin "1$O") (pinfunction "O_1$O") (pintype "passive"))
    )
    (net (code "139") (name "unconnected-(SA5-O-Pad1$O)") (class "Default")
      (node (ref "SA5") (pin "1$O") (pinfunction "O_1$O") (pintype "passive"))
    )
    (net (code "140") (name "unconnected-(SA8-O-Pad1$O)") (class "Default")
      (node (ref "SA8") (pin "1$O") (pinfunction "O_1$O") (pintype "passive"))
    )
    (net (code "141") (name "unconnected-(SA10-O-Pad1$O)") (class "Default")
      (node (ref "SA10") (pin "1$O") (pinfunction "O_1$O") (pintype "passive"))
    )
    (net (code "142") (name "unconnected-(SA13-O-Pad1$O)") (class "Default")
      (node (ref "SA13") (pin "1$O") (pinfunction "O_1$O") (pintype "passive"))
    )
    (net (code "143") (name "unconnected-(SA15-O-Pad1$O)") (class "Default")
      (node (ref "SA15") (pin "1$O") (pinfunction "O_1$O") (pintype "passive"))
    )
  )
)
